# IGOR_1.net
KiCad netlist of a schematic drawn in EAGLE
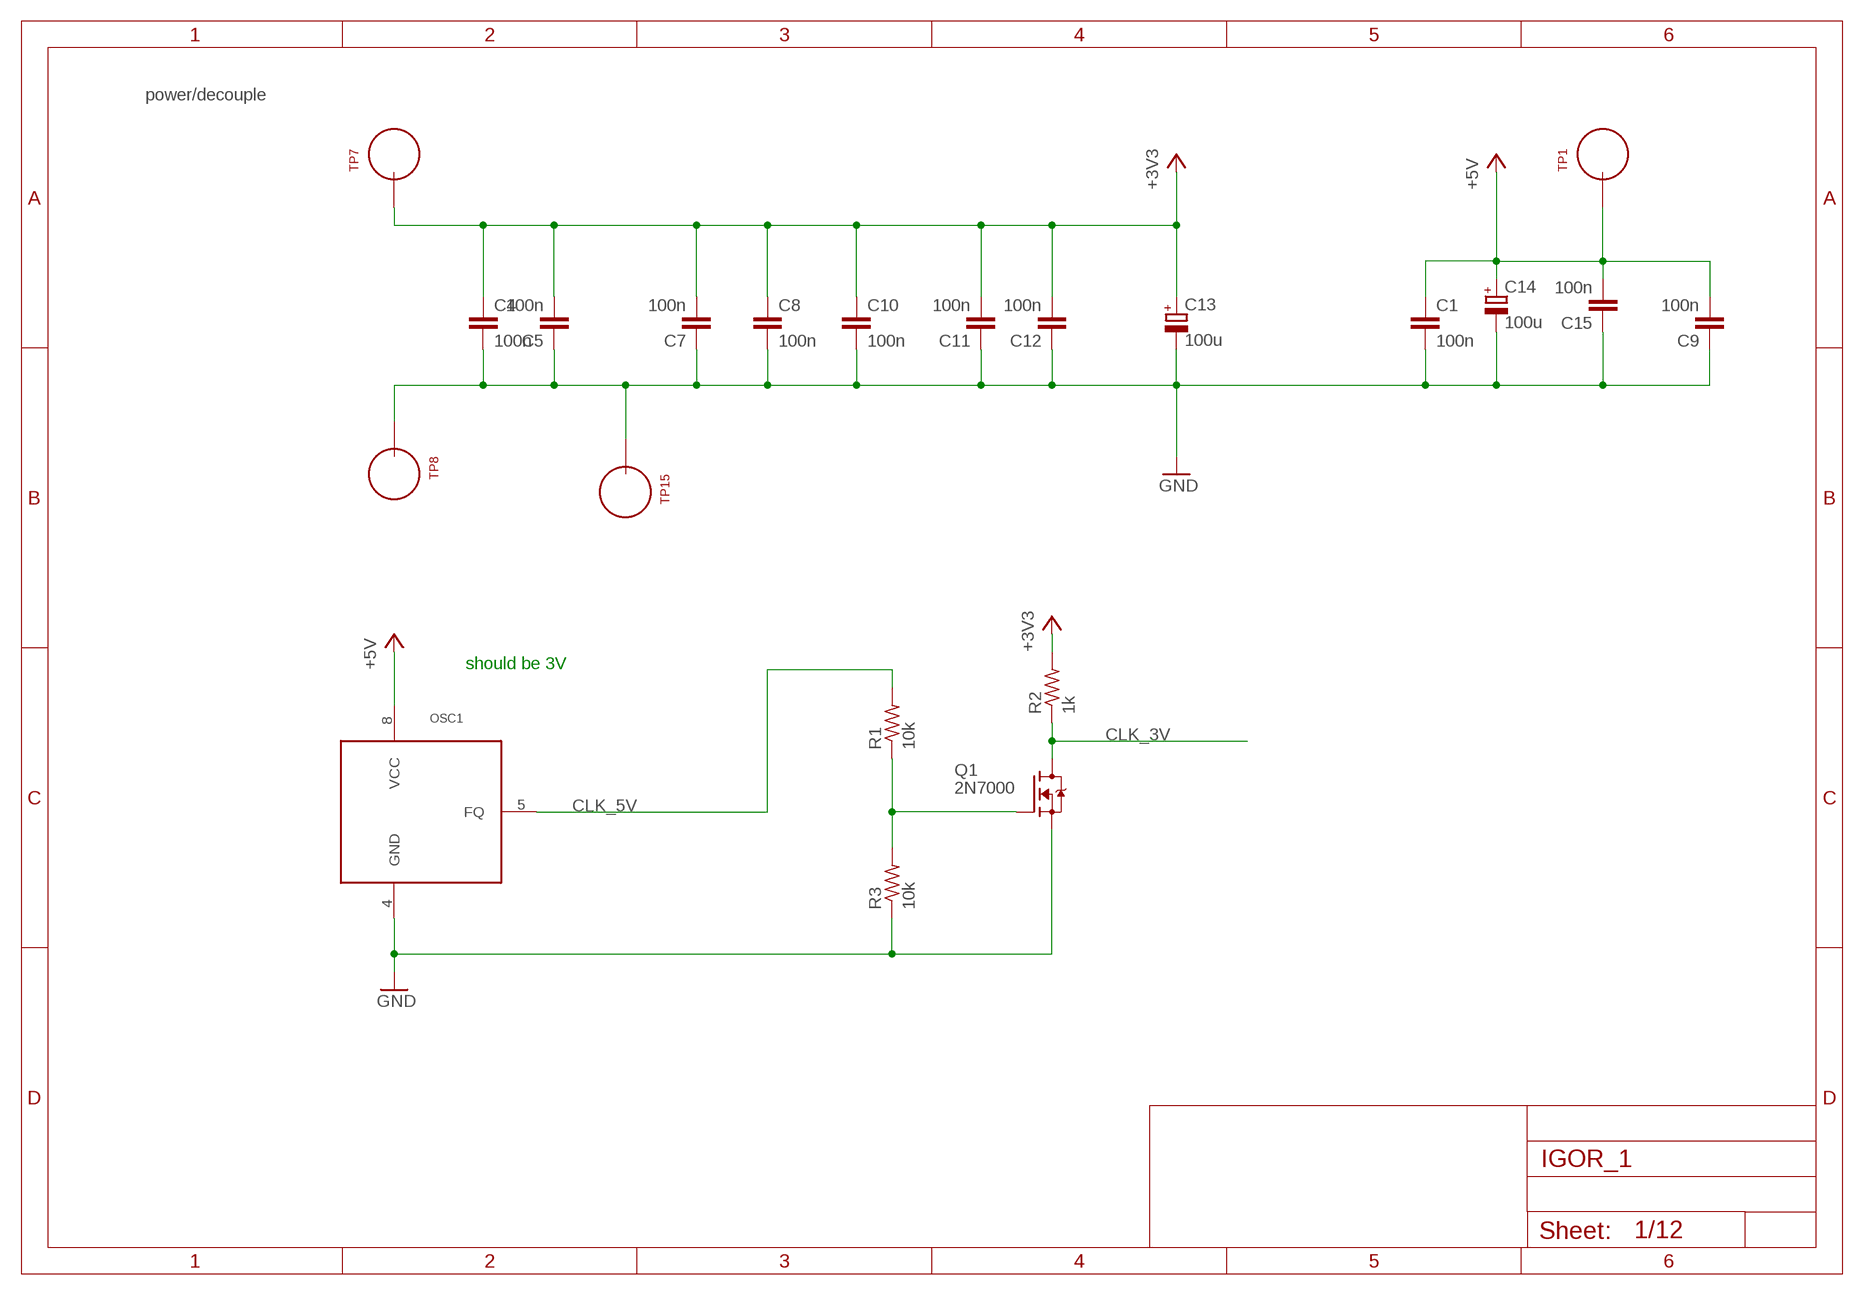
[diagram p0: schematic, sheet 1]
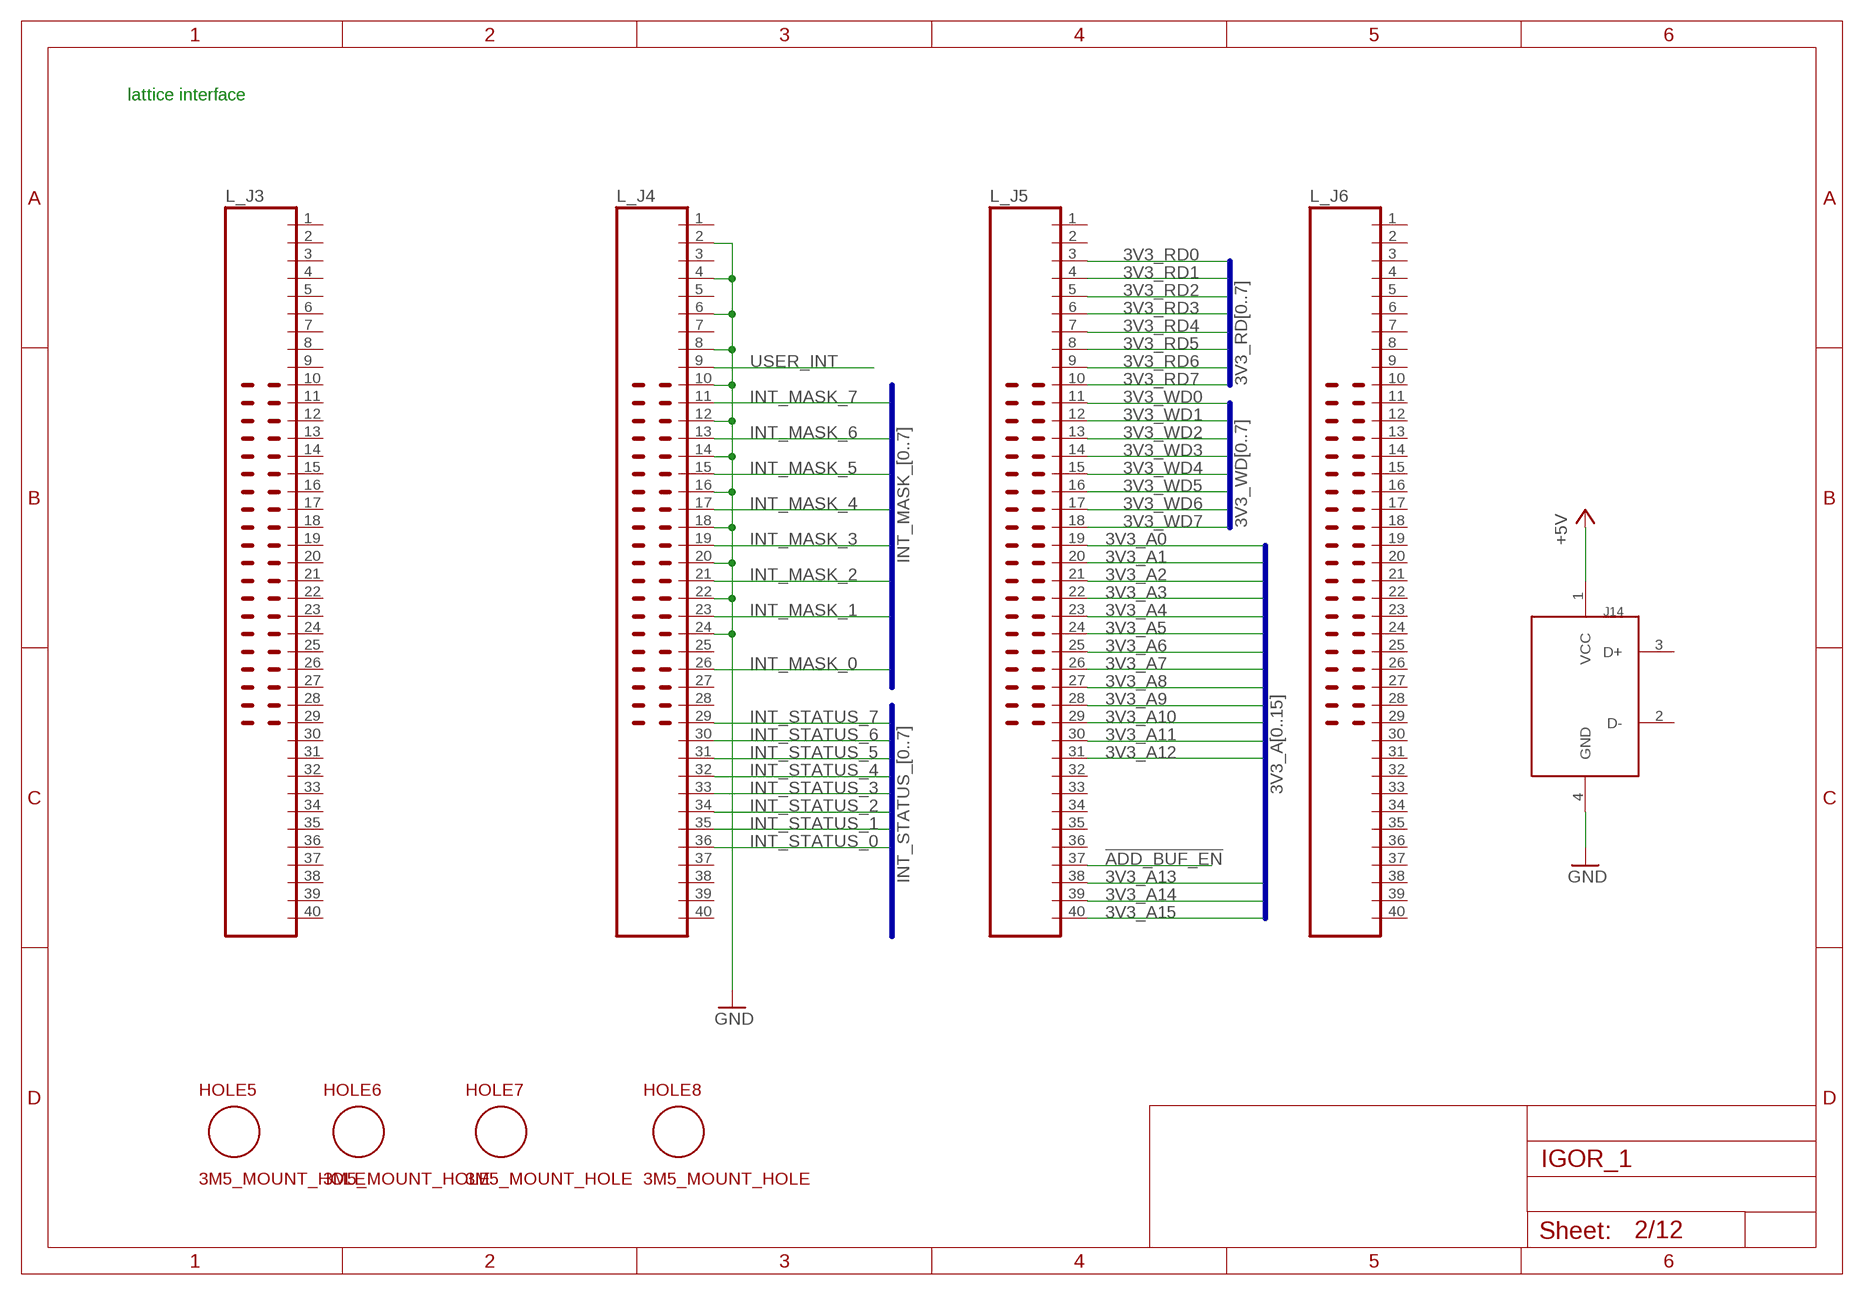
[diagram p1: schematic, sheet 2]
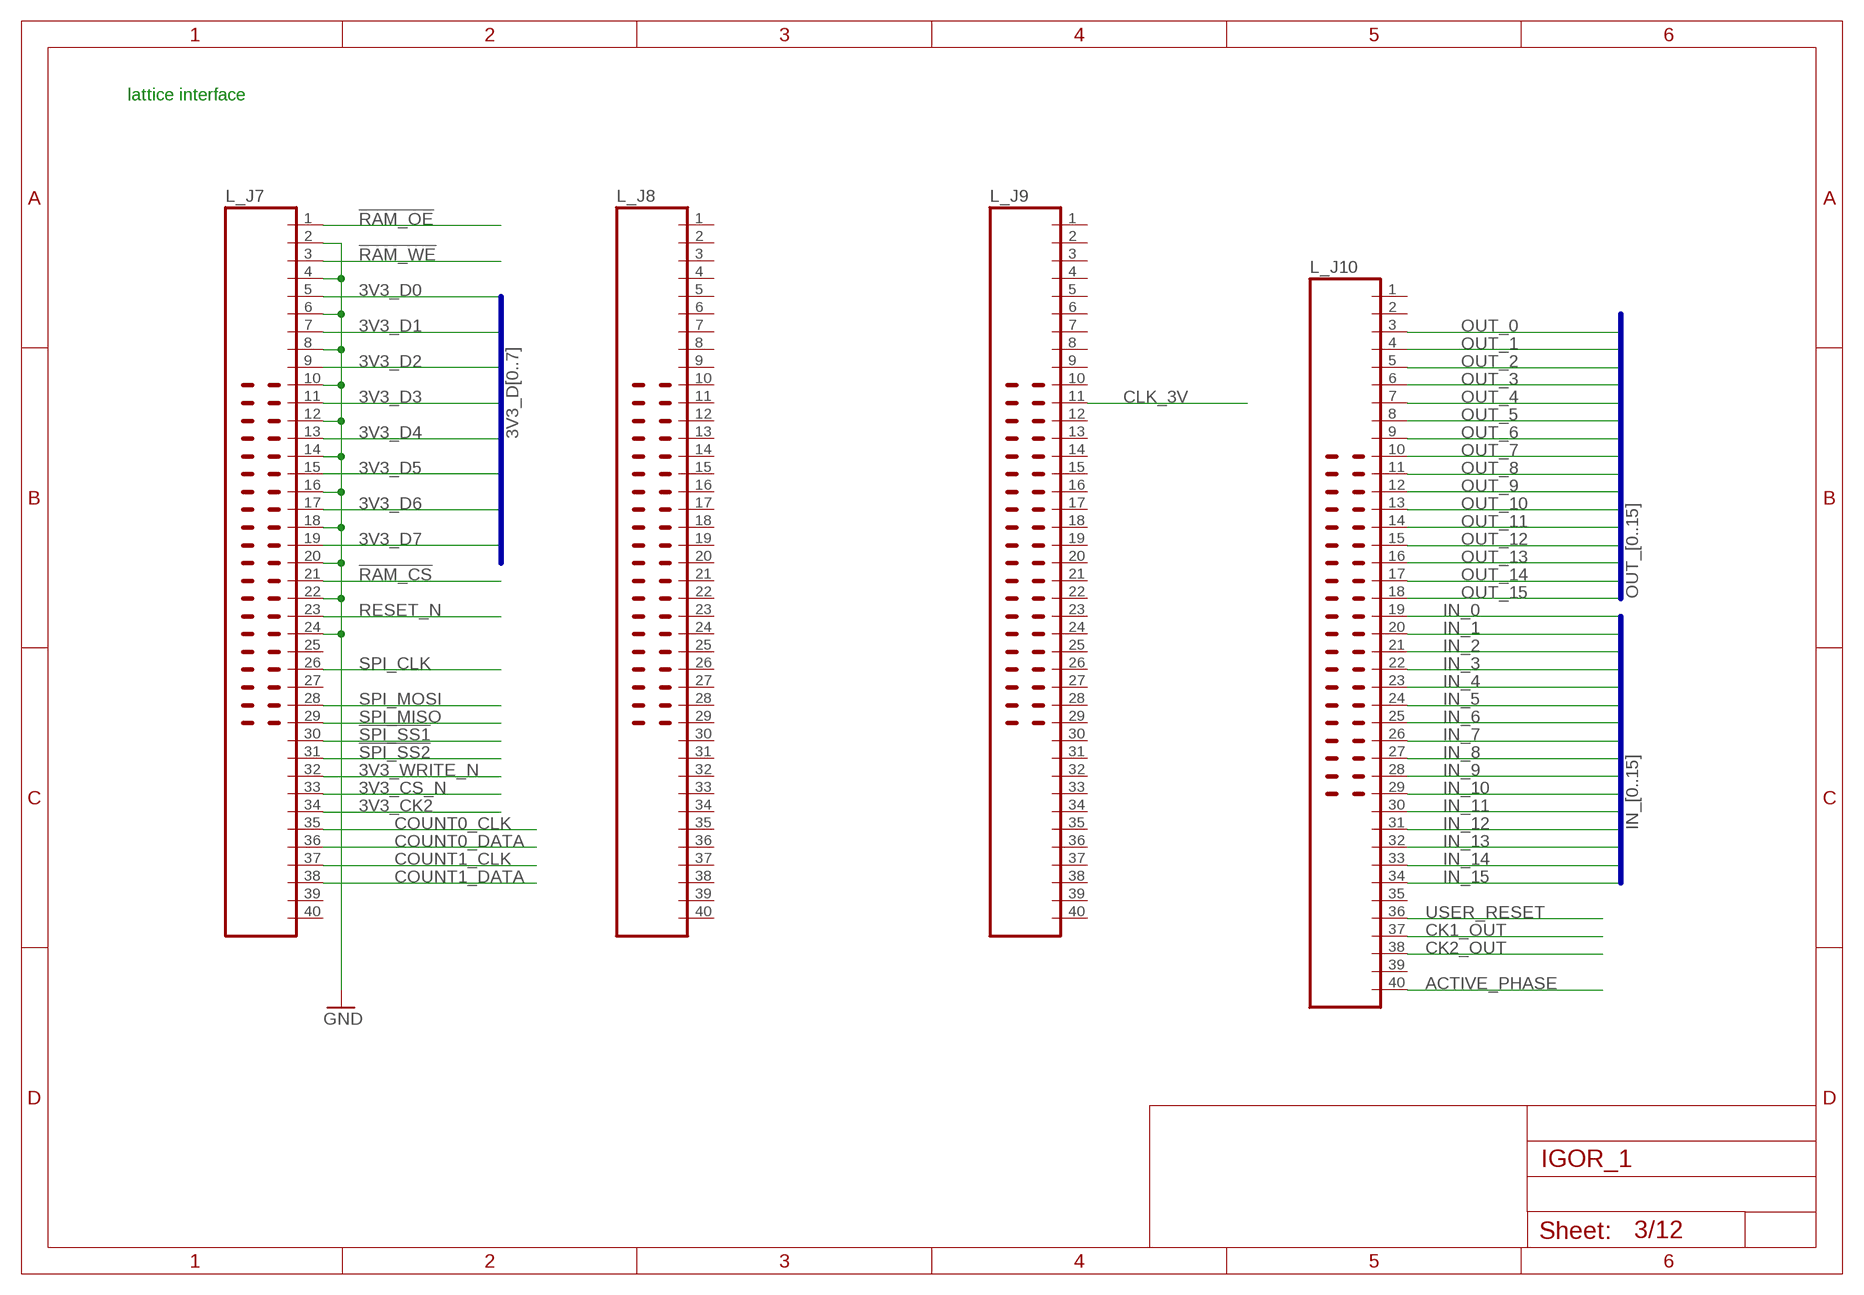
[diagram p2: schematic, sheet 3]
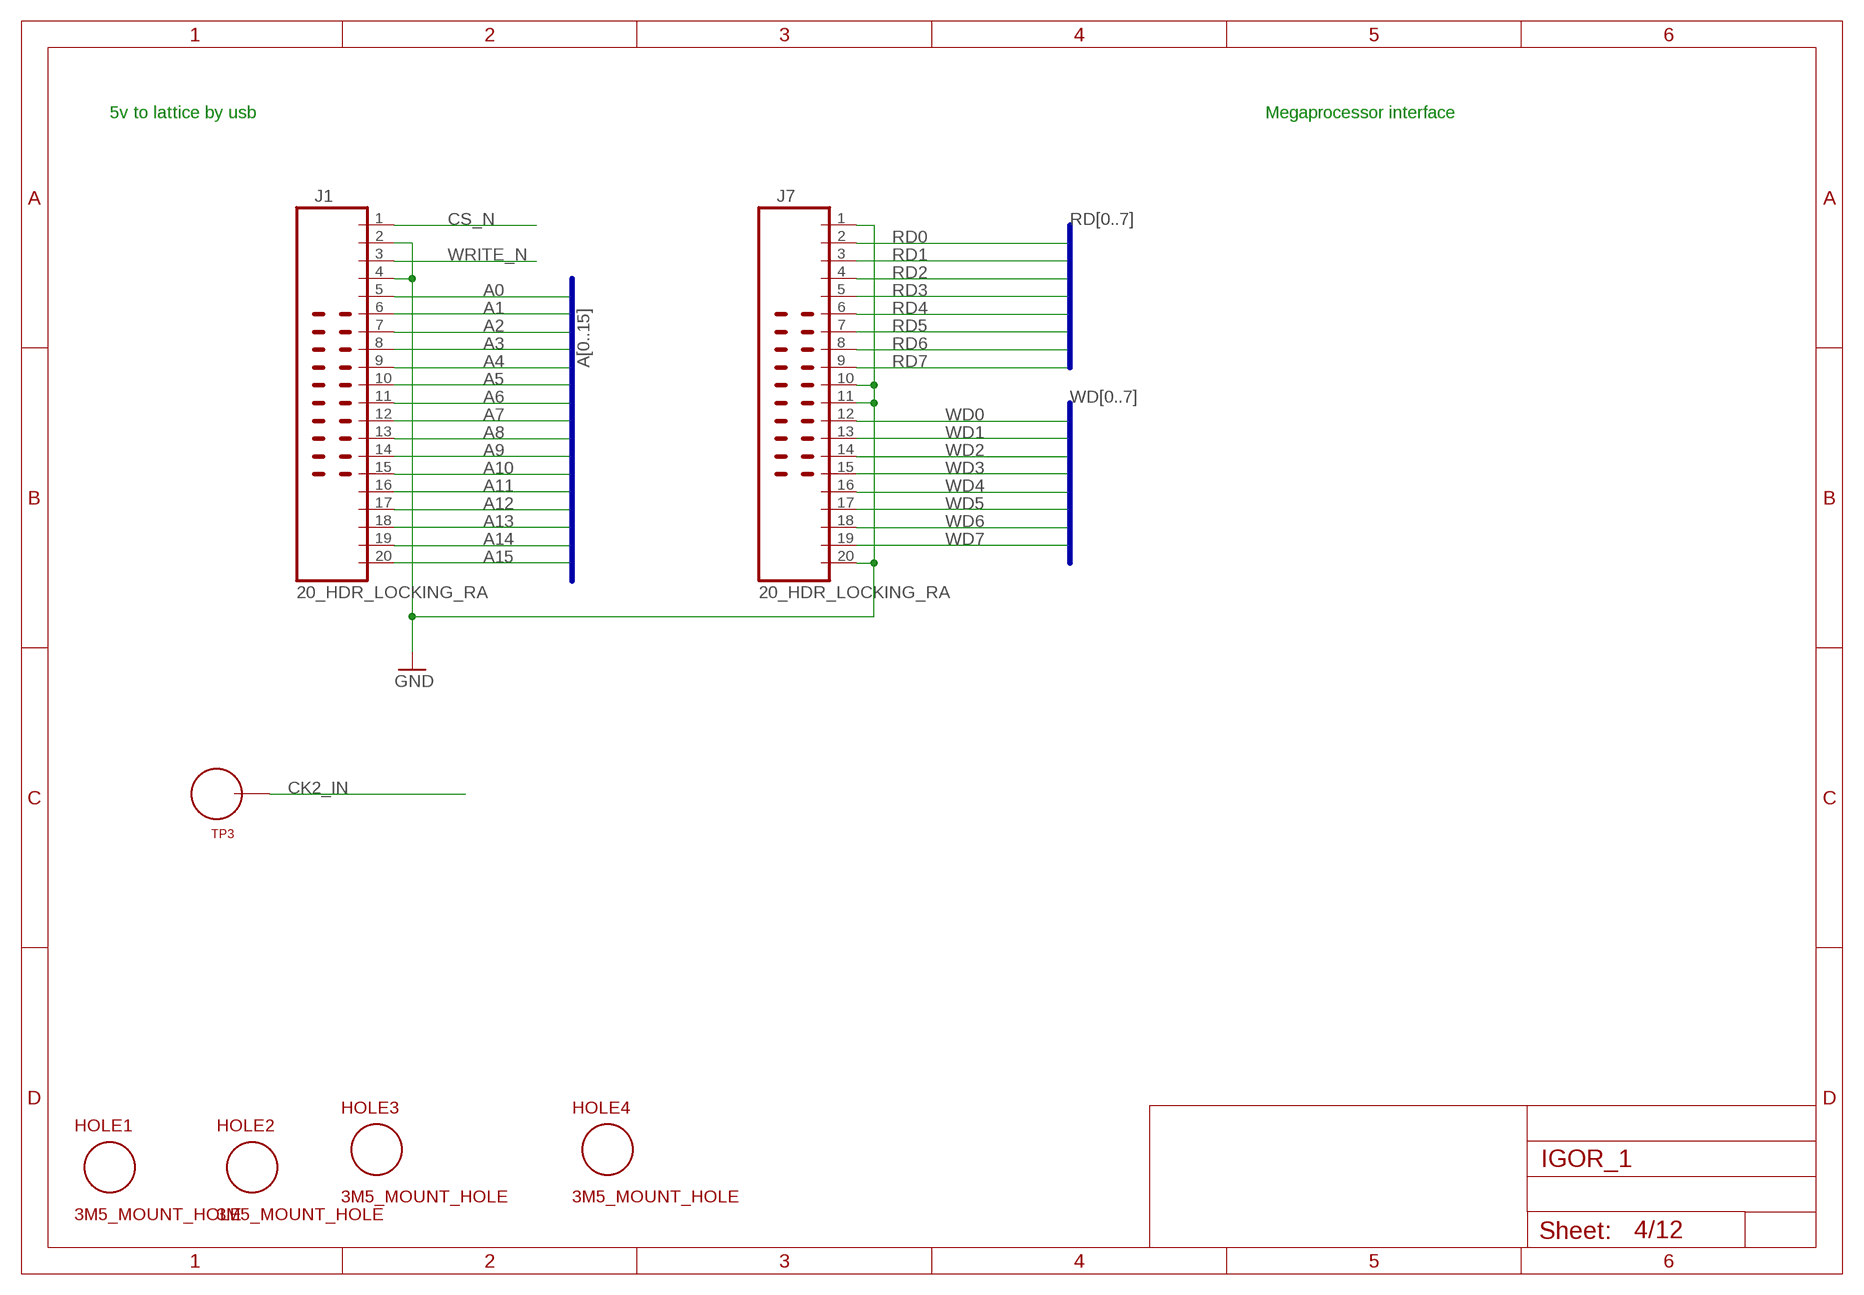
[diagram p3: schematic, sheet 4]
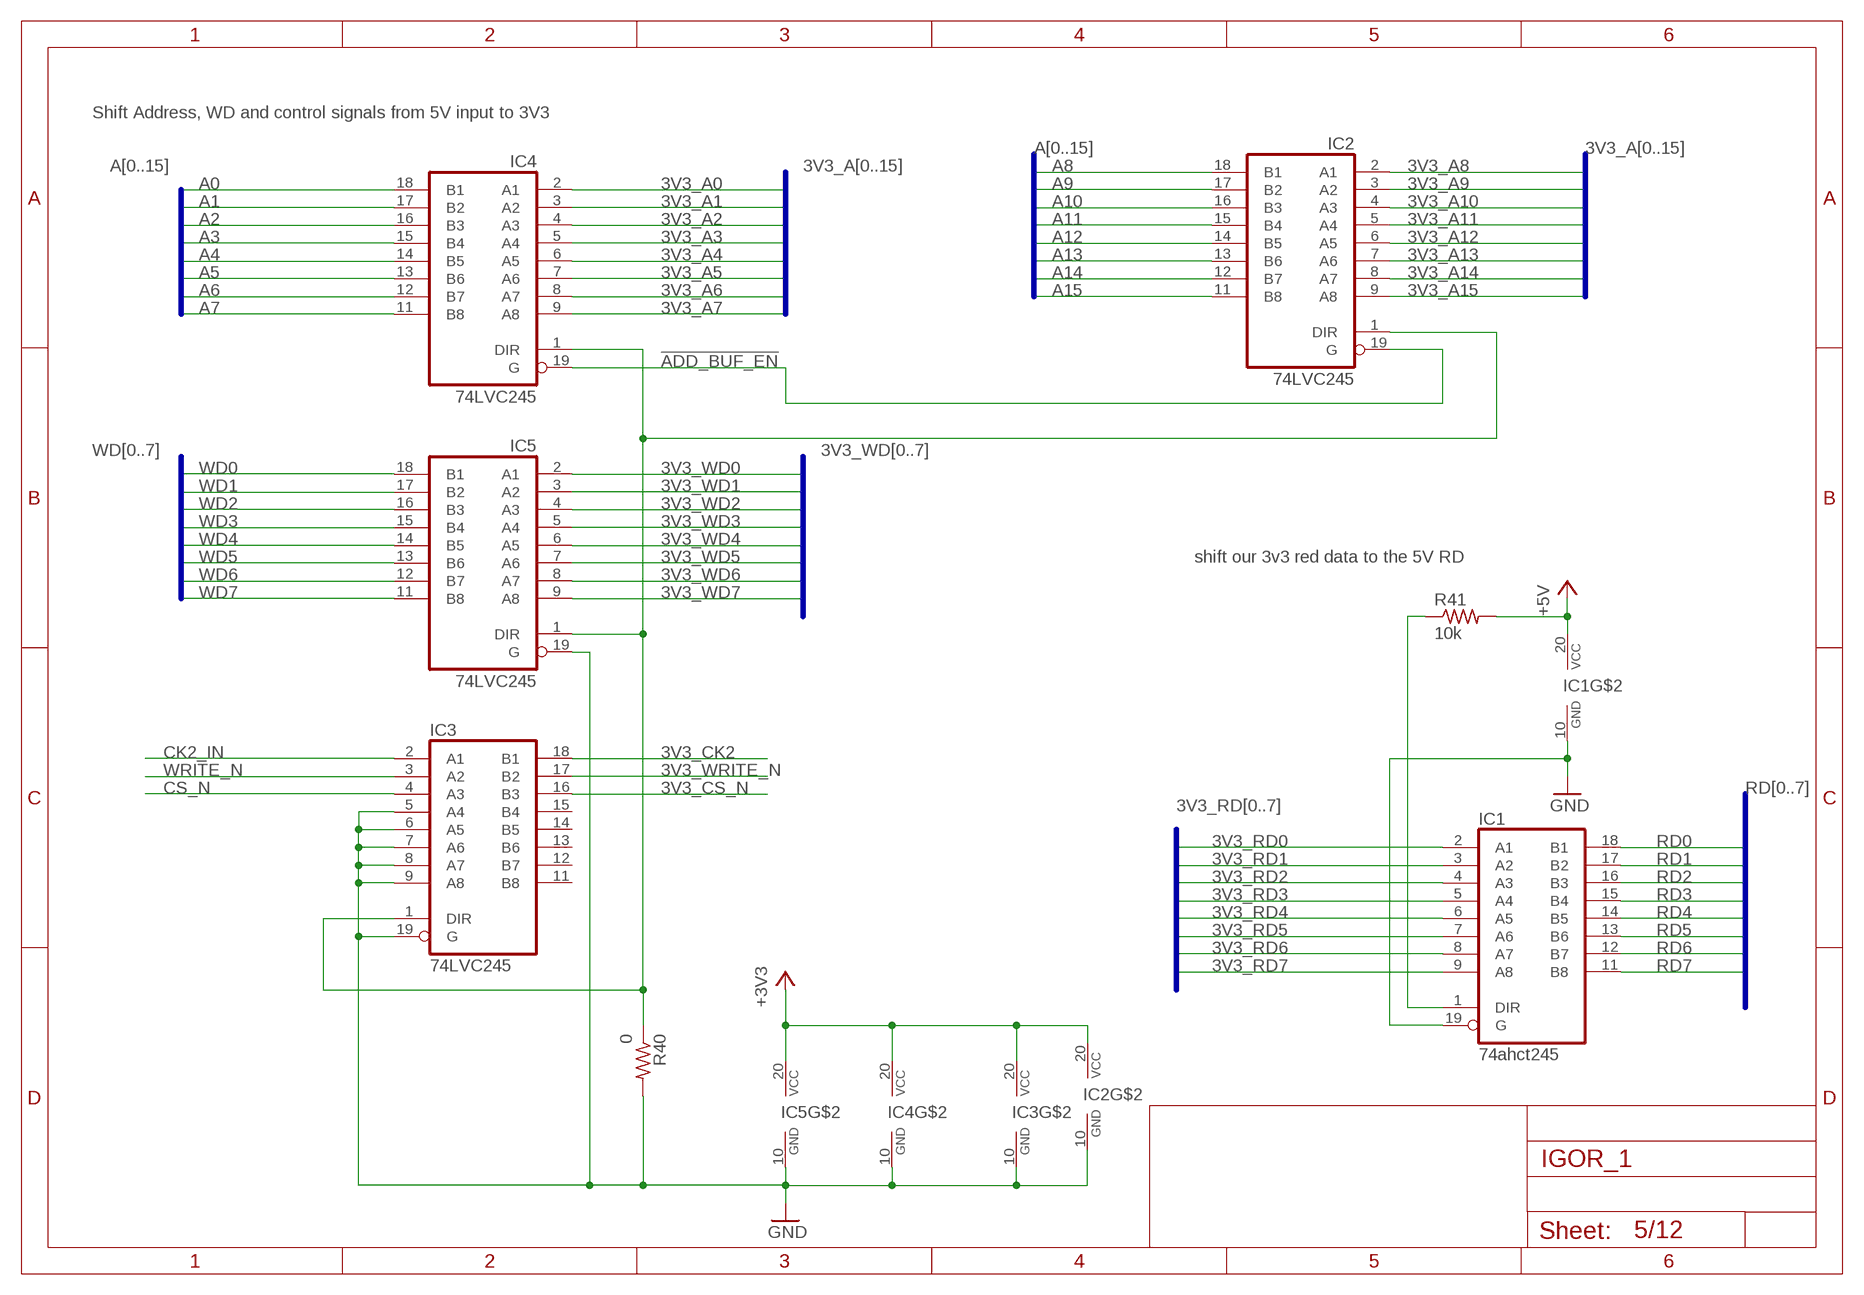
[diagram p4: schematic, sheet 5]
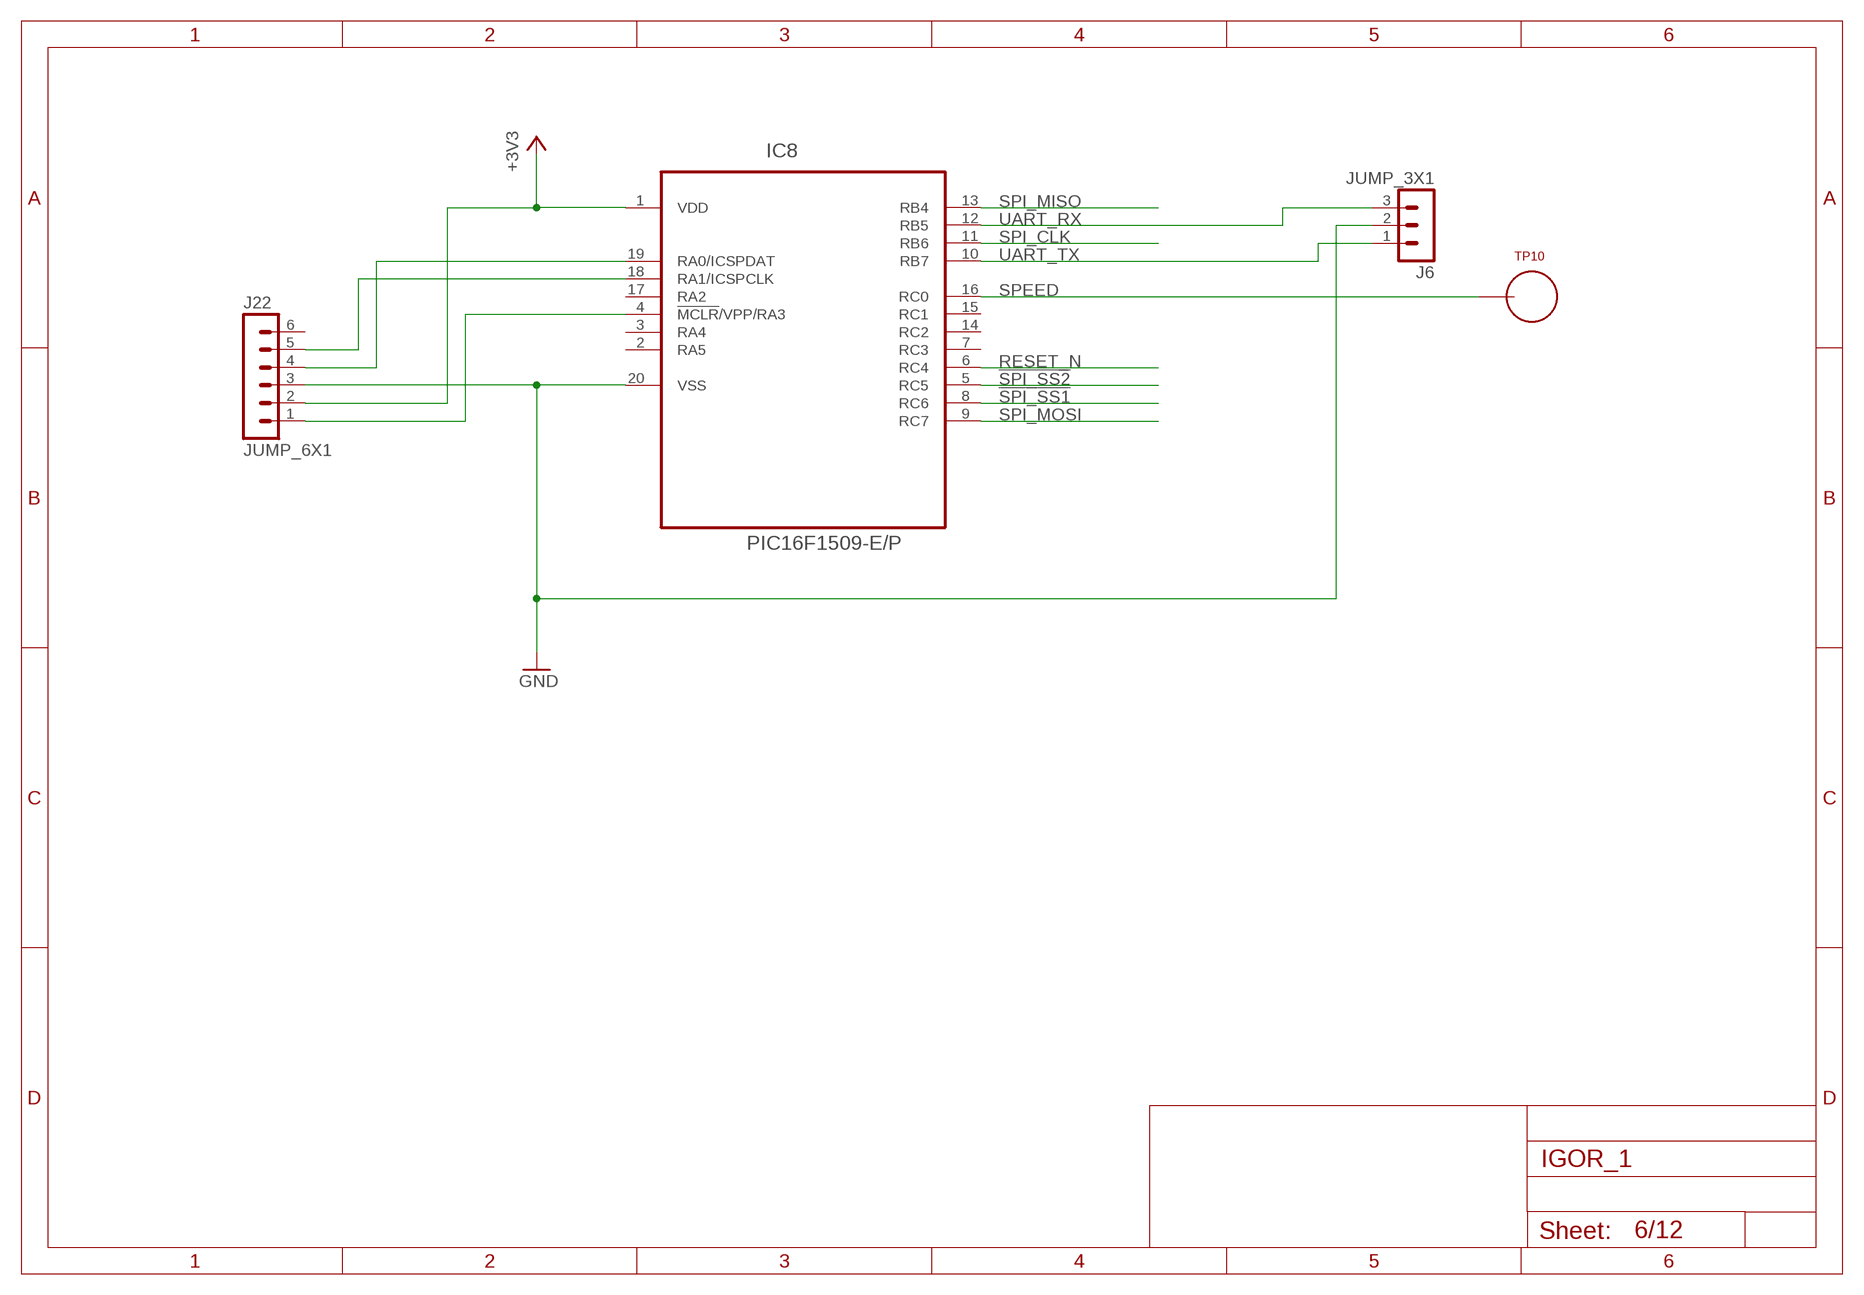
[diagram p5: schematic, sheet 6]
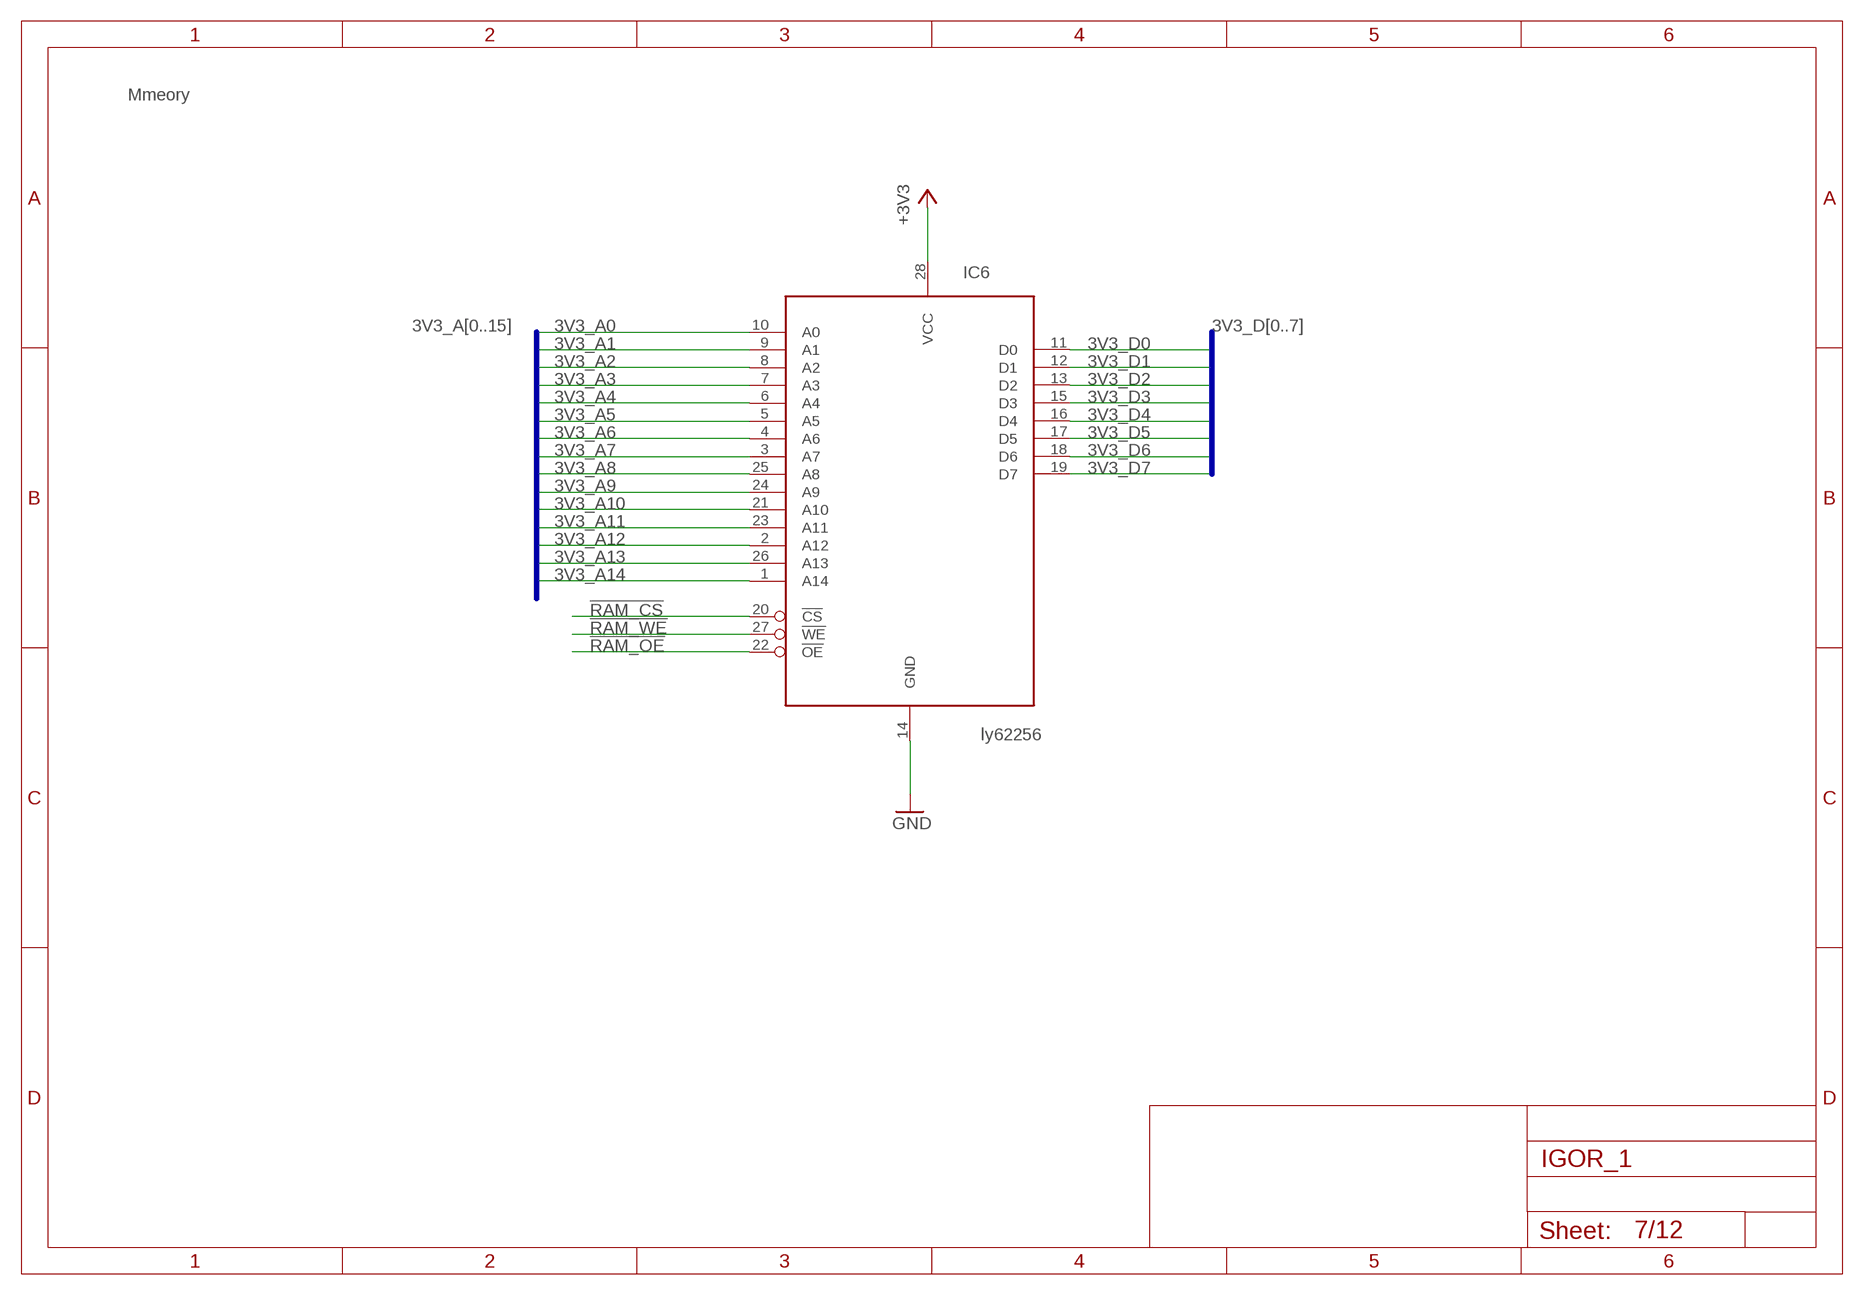
[diagram p6: schematic, sheet 7]
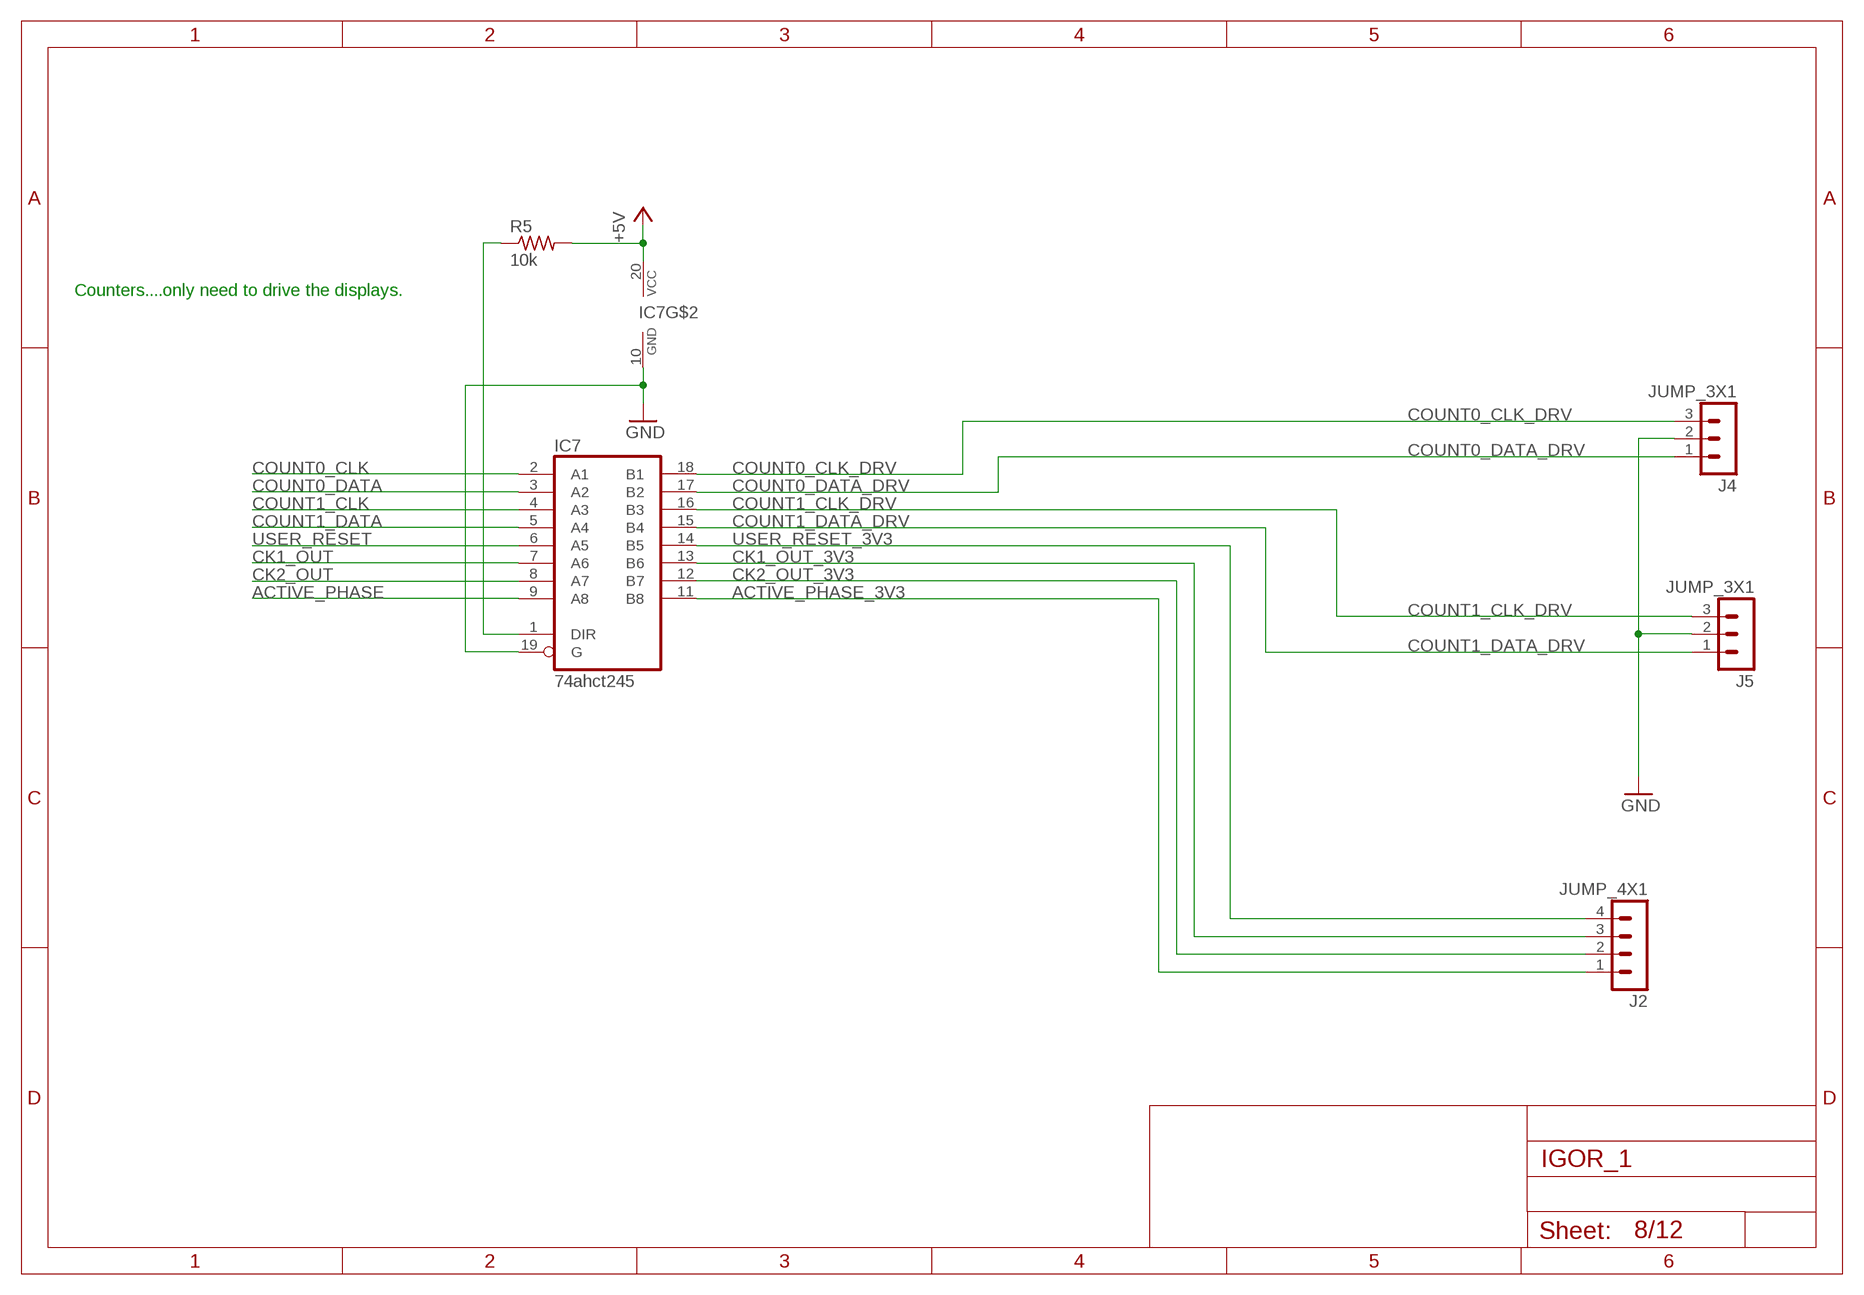
[diagram p7: schematic, sheet 8]
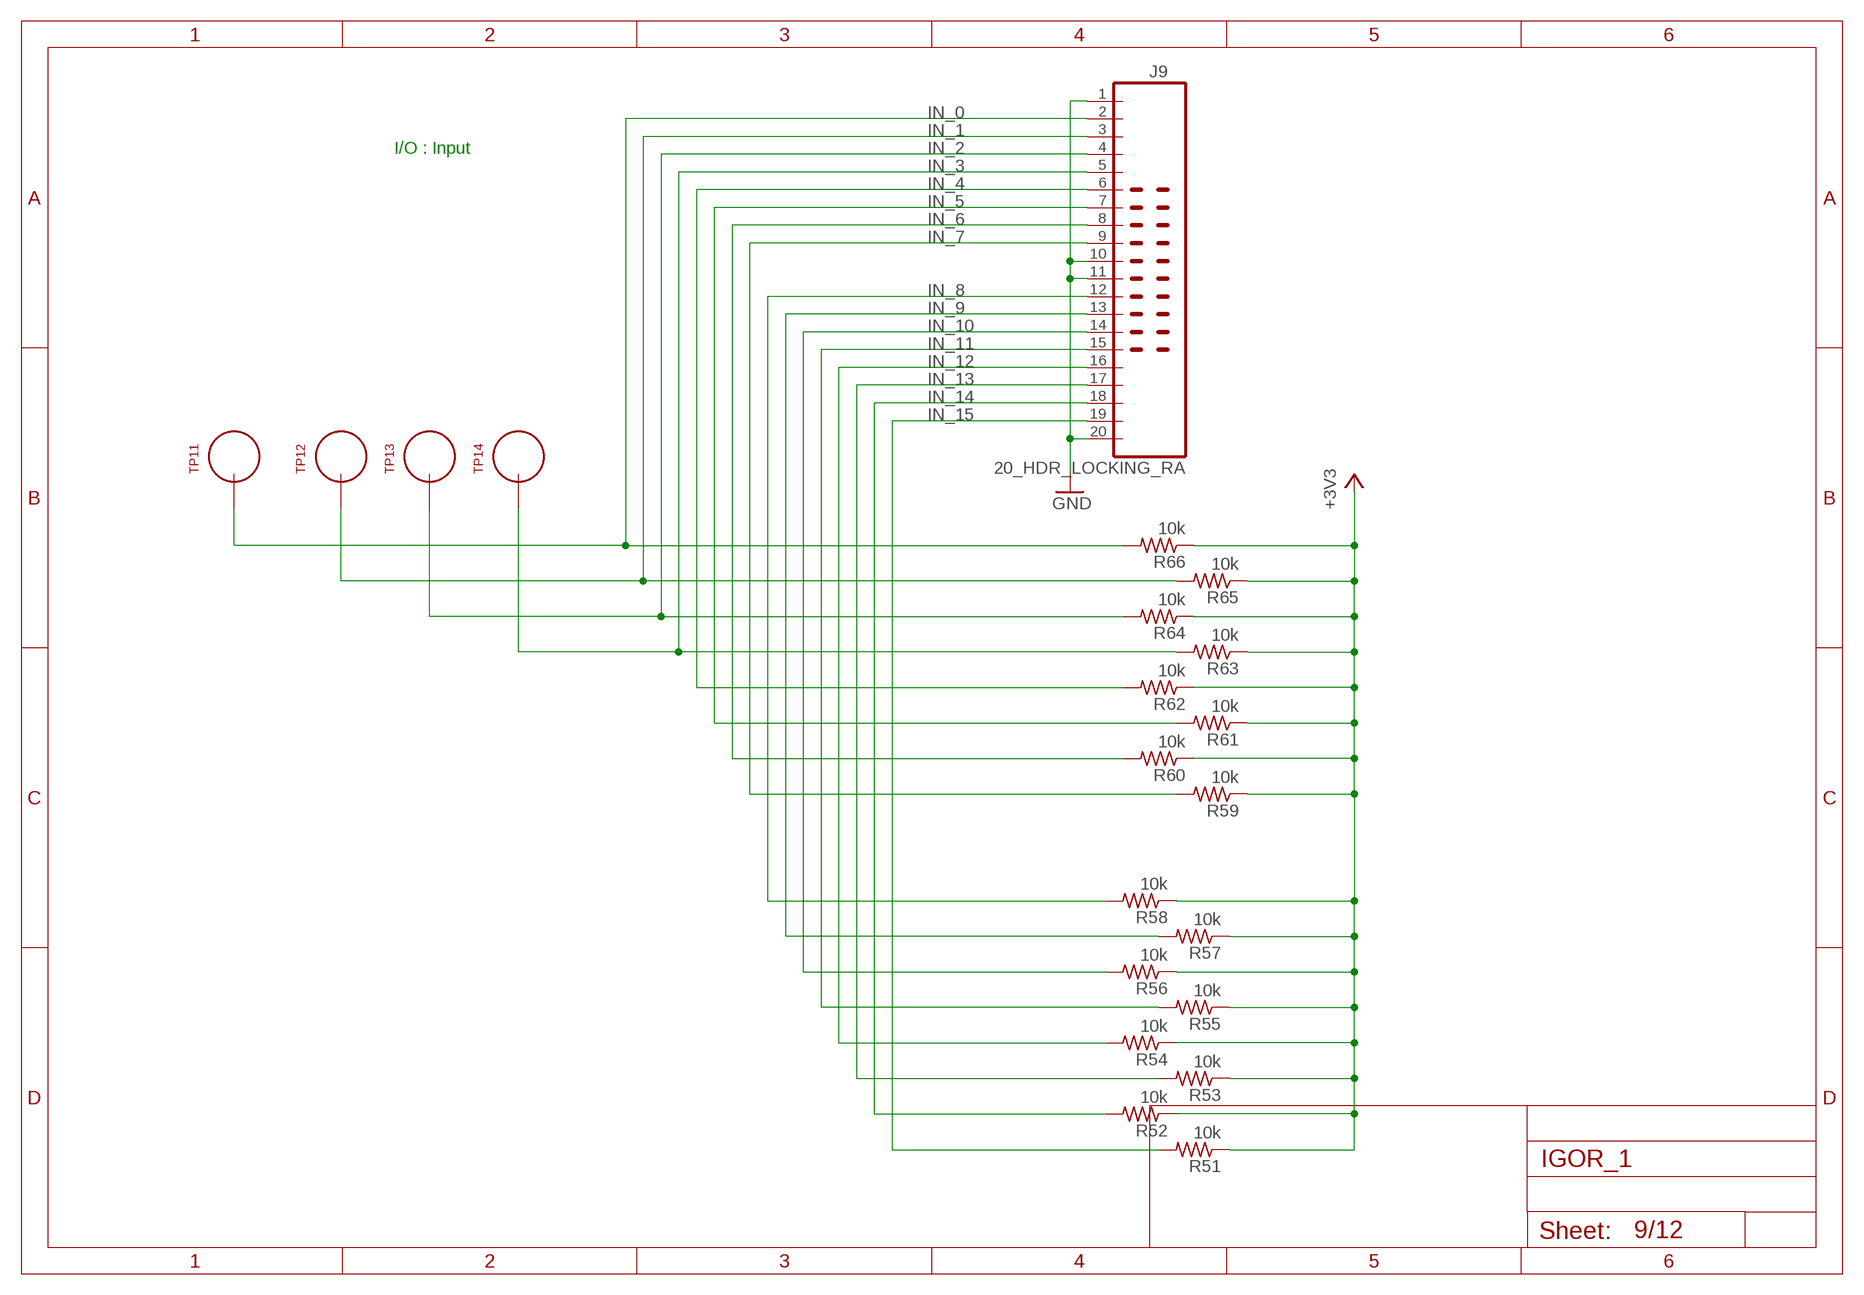
[diagram p8: schematic, sheet 9]
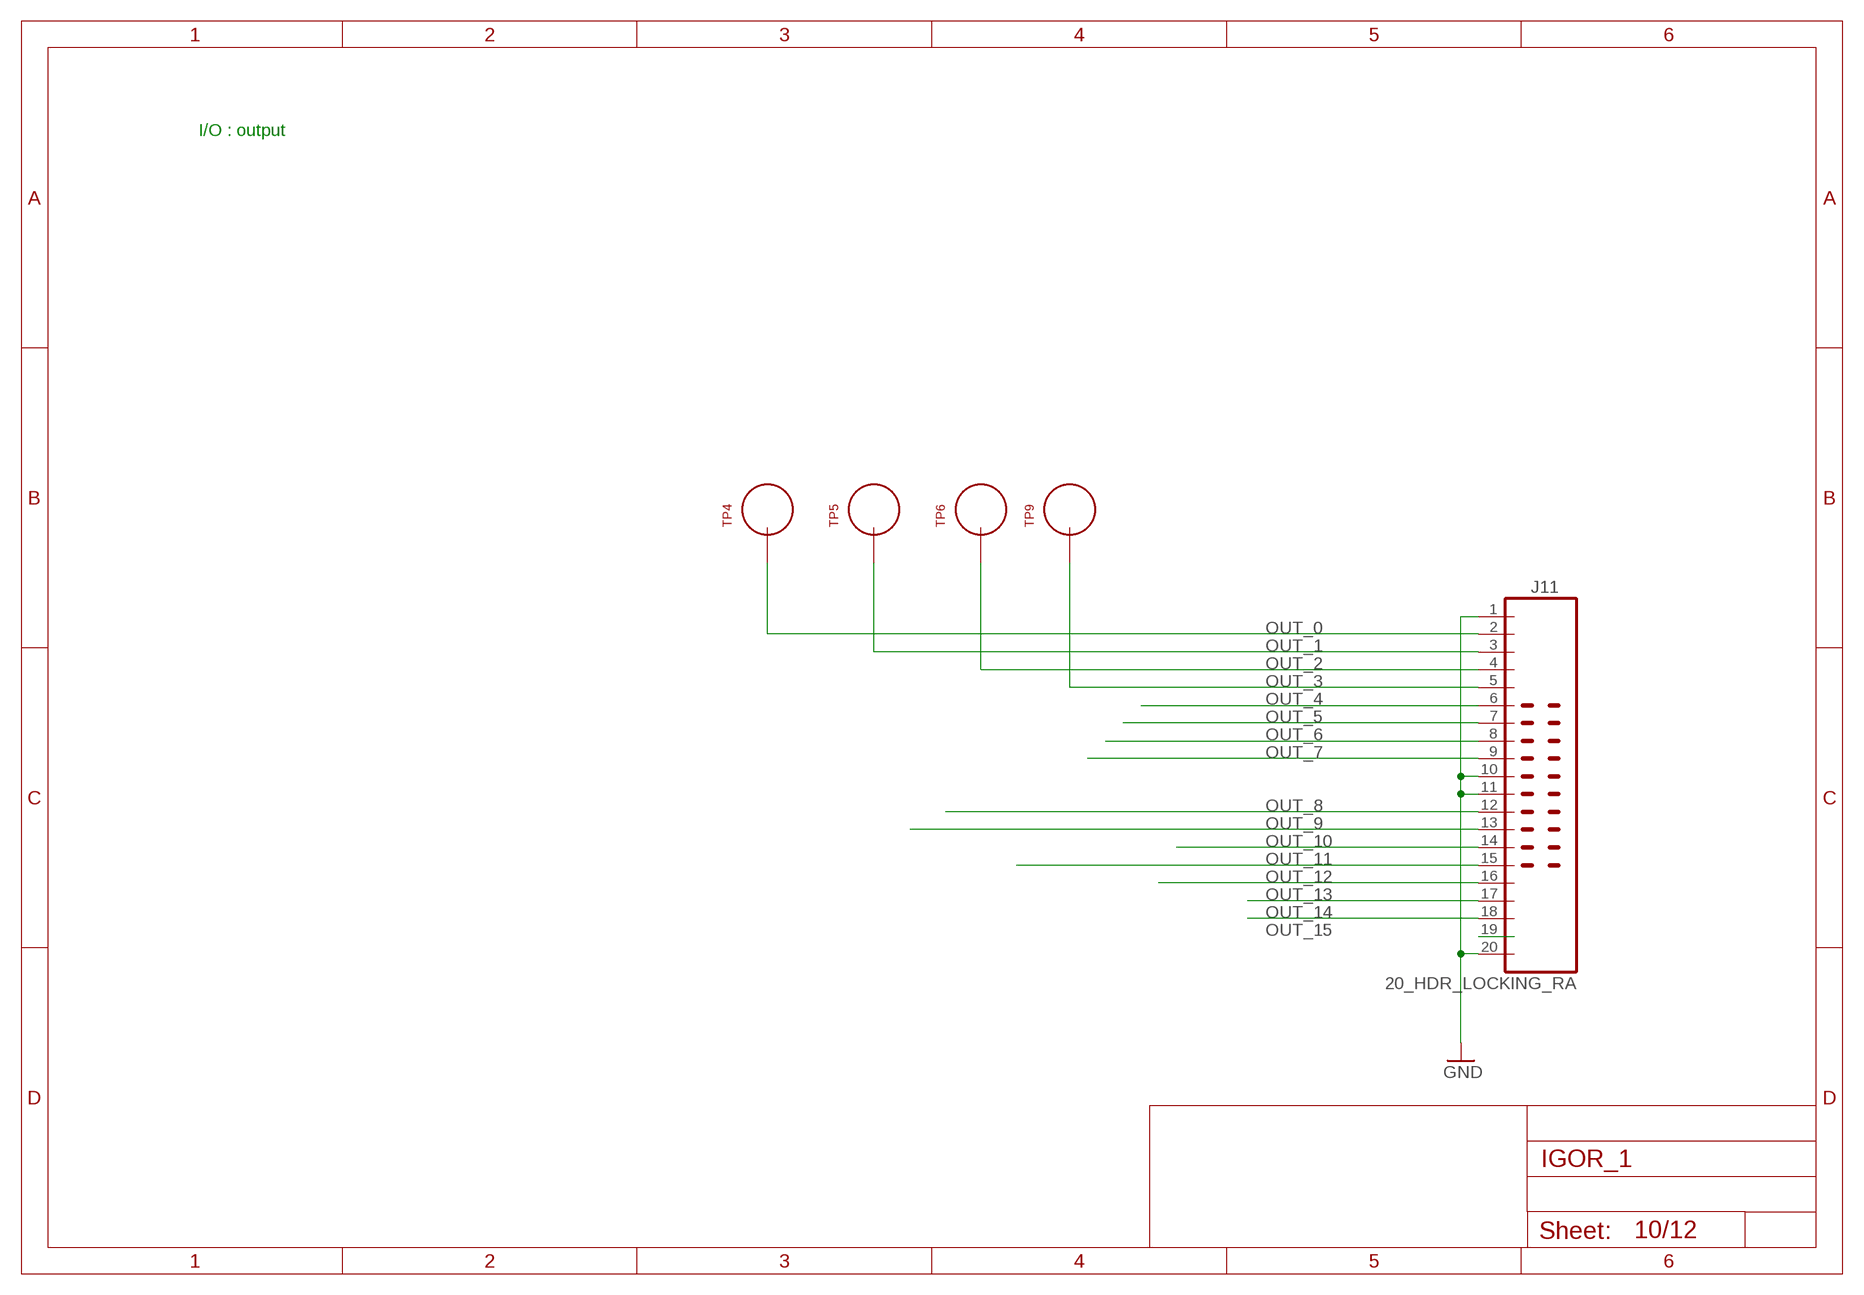
[diagram p9: schematic, sheet 10]
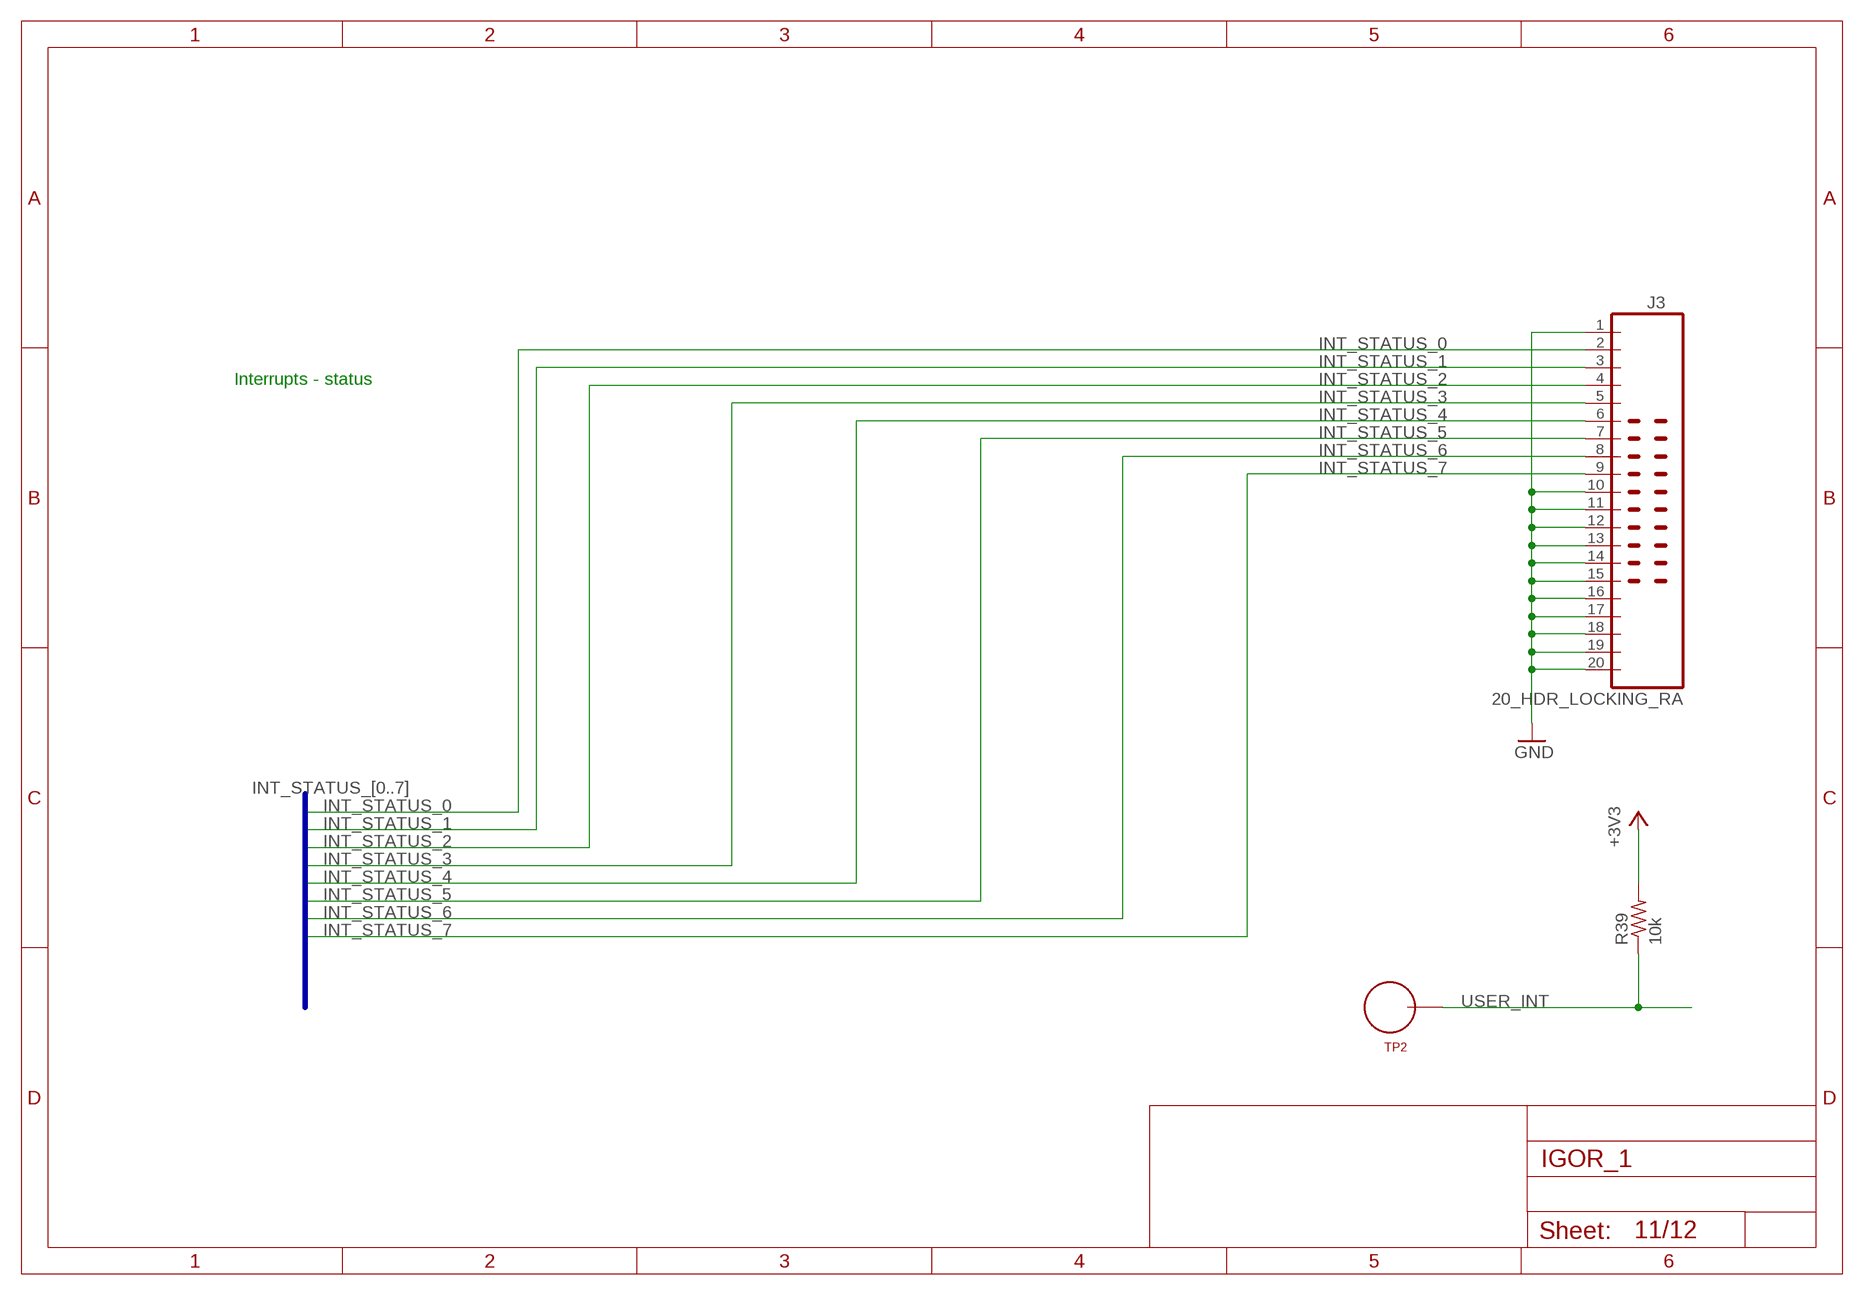
[diagram p10: schematic, sheet 11]
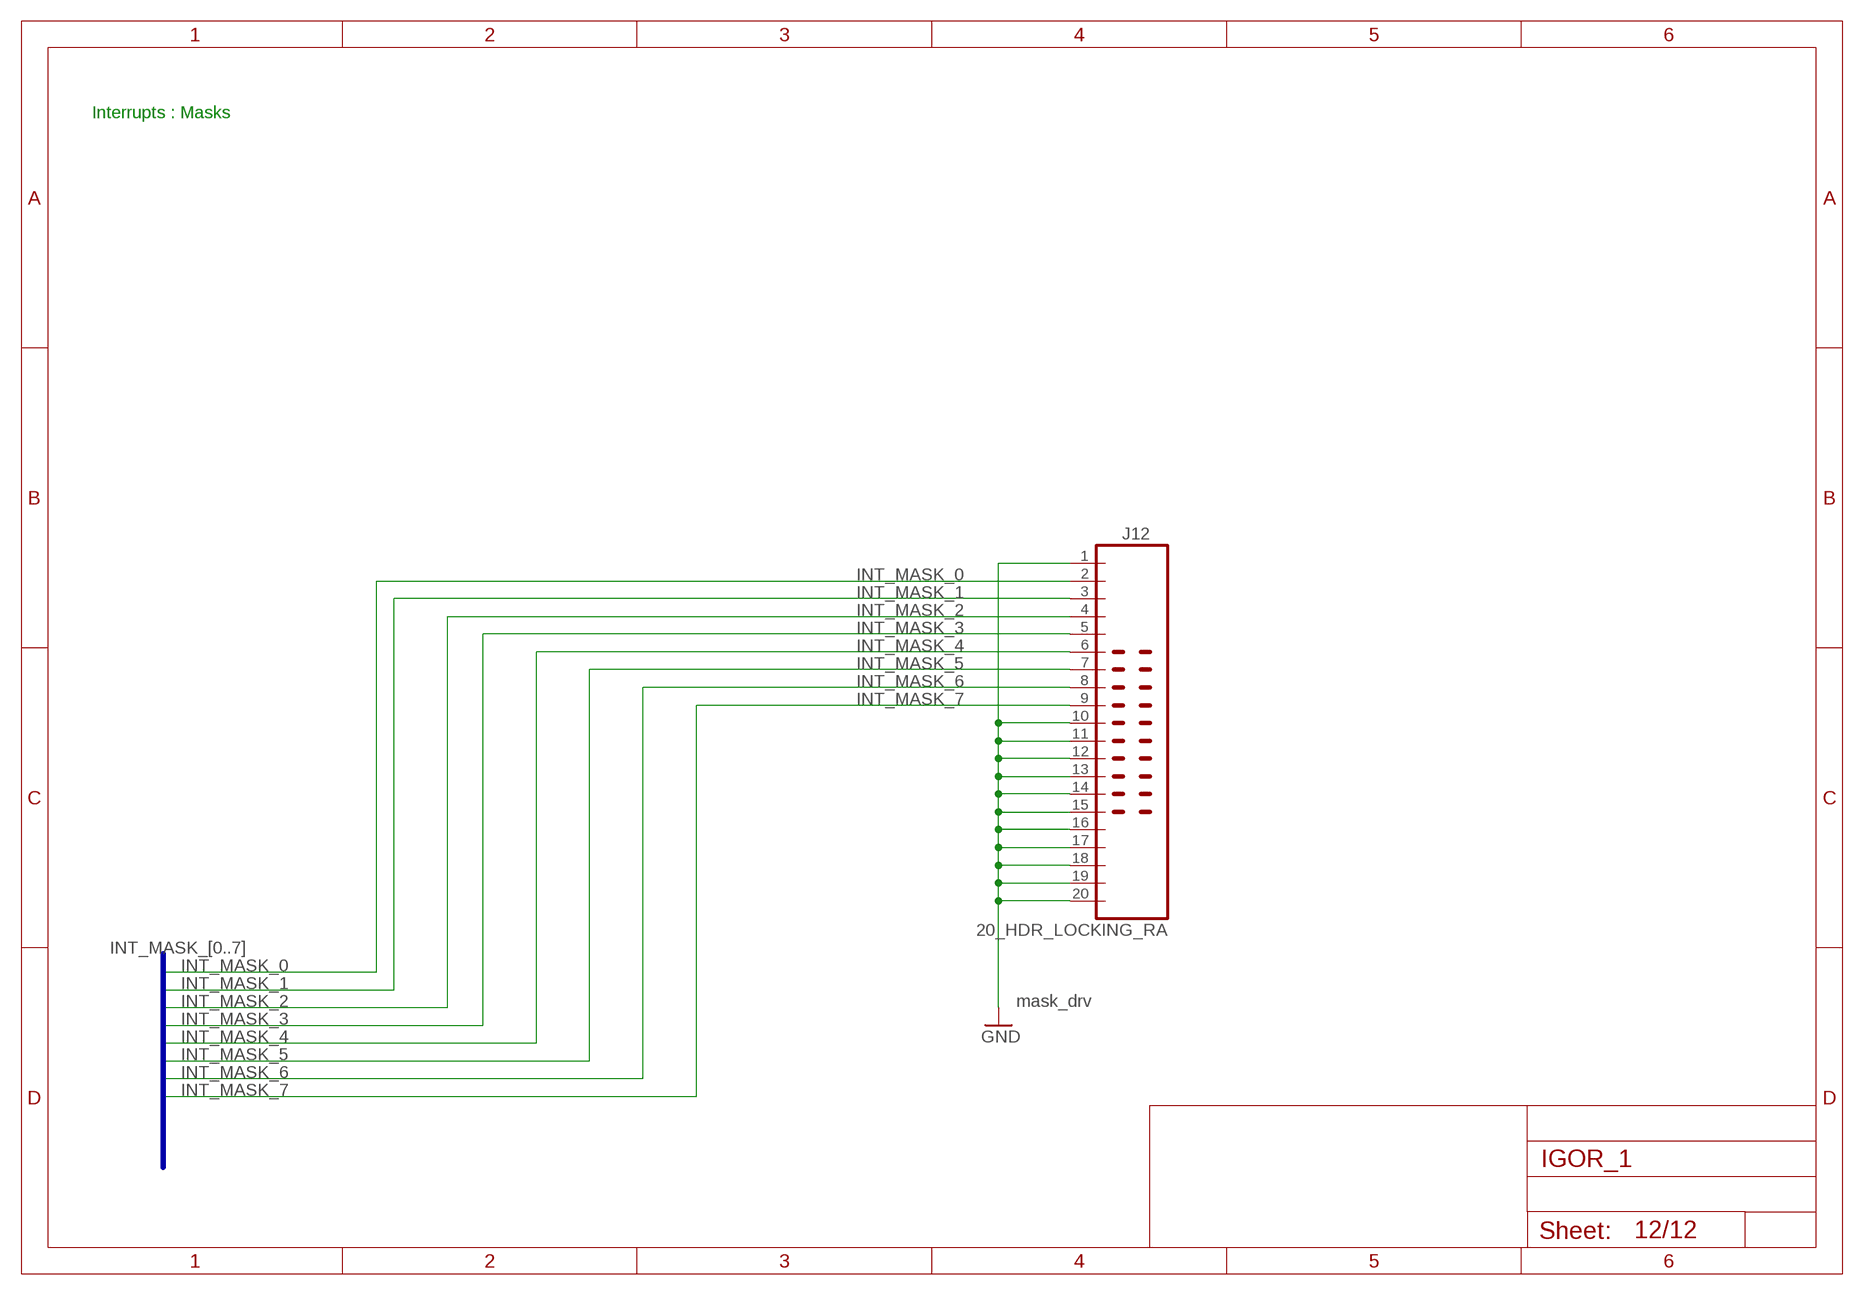
[diagram p11: schematic, sheet 12]

(export (version "E")
  (design (tool "Eeschema 10.0.6"))
  (components
    (comp (ref "IC7")
      (value "74ahct245")
      (footprint "eagle-import:DIP20")
      (libsource (lib "eagle-import") (part "74245"))
    )
    (comp (ref "J2")
      (value "JUMP_4X1")
      (footprint "eagle-import:JUMP_4X1")
      (libsource (lib "eagle-import") (part "JUMP_4X1"))
    )
    (comp (ref "J4")
      (value "JUMP_3X1")
      (footprint "eagle-import:JUMP_3X1")
      (libsource (lib "eagle-import") (part "JUMP_3X1"))
    )
    (comp (ref "J5")
      (value "JUMP_3X1")
      (footprint "eagle-import:JUMP_3X1")
      (libsource (lib "eagle-import") (part "JUMP_3X1"))
    )
    (comp (ref "R5")
      (value "10k")
      (footprint "eagle-import:R_P2INCH")
      (libsource (lib "eagle-import") (part "R_P2INCH"))
    )
    (comp (ref "HOLE5")
      (value "3M5_MOUNT_HOLE")
      (footprint "eagle-import:3P5M_HOLE")
      (libsource (lib "eagle-import") (part "3M5_MOUNT_HOLE"))
    )
    (comp (ref "HOLE6")
      (value "3M5_MOUNT_HOLE")
      (footprint "eagle-import:3P5M_HOLE")
      (libsource (lib "eagle-import") (part "3M5_MOUNT_HOLE"))
    )
    (comp (ref "HOLE7")
      (value "3M5_MOUNT_HOLE")
      (footprint "eagle-import:3P5M_HOLE")
      (libsource (lib "eagle-import") (part "3M5_MOUNT_HOLE"))
    )
    (comp (ref "HOLE8")
      (value "3M5_MOUNT_HOLE")
      (footprint "eagle-import:3P5M_HOLE")
      (libsource (lib "eagle-import") (part "3M5_MOUNT_HOLE"))
    )
    (comp (ref "J14")
      (value "USB_TYPE_A")
      (footprint "eagle-import:USB_TYPE_A")
      (libsource (lib "eagle-import") (part "USB_TYPE_A"))
    )
    (comp (ref "L_J3")
      (value "JUMP_20X2")
      (footprint "eagle-import:JUMP_20X2")
      (libsource (lib "eagle-import") (part "JUMP_20X2"))
    )
    (comp (ref "L_J4")
      (value "JUMP_20X2")
      (footprint "eagle-import:JUMP_20X2")
      (libsource (lib "eagle-import") (part "JUMP_20X2"))
    )
    (comp (ref "L_J5")
      (value "JUMP_20X2")
      (footprint "eagle-import:JUMP_20X2")
      (libsource (lib "eagle-import") (part "JUMP_20X2"))
    )
    (comp (ref "L_J6")
      (value "JUMP_20X2")
      (footprint "eagle-import:JUMP_20X2")
      (libsource (lib "eagle-import") (part "JUMP_20X2"))
    )
    (comp (ref "J11")
      (value "20_HDR_LOCKING_RA")
      (footprint "eagle-import:20_HDR_LOCKING_RA")
      (libsource (lib "eagle-import") (part "20_HDR_LOCKING_RA"))
    )
    (comp (ref "TP4")
      (value "TEST_LOOP")
      (footprint "eagle-import:TEST_LOOP")
      (libsource (lib "eagle-import") (part "TEST_LOOP"))
    )
    (comp (ref "TP5")
      (value "TEST_LOOP")
      (footprint "eagle-import:TEST_LOOP")
      (libsource (lib "eagle-import") (part "TEST_LOOP"))
    )
    (comp (ref "TP6")
      (value "TEST_LOOP")
      (footprint "eagle-import:TEST_LOOP")
      (libsource (lib "eagle-import") (part "TEST_LOOP"))
    )
    (comp (ref "TP9")
      (value "TEST_LOOP")
      (footprint "eagle-import:TEST_LOOP")
      (libsource (lib "eagle-import") (part "TEST_LOOP"))
    )
    (comp (ref "C1")
      (value "100n")
      (footprint "eagle-import:CAP_P2INCH")
      (libsource (lib "eagle-import") (part "C_P2INCH"))
    )
    (comp (ref "C4")
      (value "100n")
      (footprint "eagle-import:CAP_P2INCH")
      (libsource (lib "eagle-import") (part "C_P2INCH"))
    )
    (comp (ref "C5")
      (value "100n")
      (footprint "eagle-import:CAP_P2INCH")
      (libsource (lib "eagle-import") (part "C_P2INCH"))
    )
    (comp (ref "C7")
      (value "100n")
      (footprint "eagle-import:CAP_P2INCH")
      (libsource (lib "eagle-import") (part "C_P2INCH"))
    )
    (comp (ref "C8")
      (value "100n")
      (footprint "eagle-import:CAP_P2INCH")
      (libsource (lib "eagle-import") (part "C_P2INCH"))
    )
    (comp (ref "C9")
      (value "100n")
      (footprint "eagle-import:CAP_P2INCH")
      (libsource (lib "eagle-import") (part "C_P2INCH"))
    )
    (comp (ref "C10")
      (value "100n")
      (footprint "eagle-import:CAP_P2INCH")
      (libsource (lib "eagle-import") (part "C_P2INCH"))
    )
    (comp (ref "C11")
      (value "100n")
      (footprint "eagle-import:CAP_P2INCH")
      (libsource (lib "eagle-import") (part "C_P2INCH"))
    )
    (comp (ref "C12")
      (value "100n")
      (footprint "eagle-import:CAP_P2INCH")
      (libsource (lib "eagle-import") (part "C_P2INCH"))
    )
    (comp (ref "C13")
      (value "100u")
      (footprint "eagle-import:POLARISED_CAP_2P5_6P3MM")
      (libsource (lib "eagle-import") (part "POLARISED_CAP_2P5_6P3MM"))
    )
    (comp (ref "C14")
      (value "100u")
      (footprint "eagle-import:POLARISED_CAP_2P5_6P3MM")
      (libsource (lib "eagle-import") (part "POLARISED_CAP_2P5_6P3MM"))
    )
    (comp (ref "C15")
      (value "100n")
      (footprint "eagle-import:CAP_P2INCH")
      (libsource (lib "eagle-import") (part "C_P2INCH"))
    )
    (comp (ref "OSC1")
      (value "OSC_12P9_MM")
      (footprint "eagle-import:OSC_12P9_MM")
      (libsource (lib "eagle-import") (part "OSC_12P9_MM"))
    )
    (comp (ref "Q1")
      (value "2N7000")
      (footprint "eagle-import:TO92-DGS")
      (libsource (lib "eagle-import") (part "2N7000"))
    )
    (comp (ref "R1")
      (value "10k")
      (footprint "eagle-import:R_P2INCH")
      (libsource (lib "eagle-import") (part "R_P2INCH"))
    )
    (comp (ref "R2")
      (value "1k")
      (footprint "eagle-import:R_P2INCH")
      (libsource (lib "eagle-import") (part "R_P2INCH"))
    )
    (comp (ref "R3")
      (value "10k")
      (footprint "eagle-import:R_P2INCH")
      (libsource (lib "eagle-import") (part "R_P2INCH"))
    )
    (comp (ref "TP1")
      (value "TEST_LOOP")
      (footprint "eagle-import:TEST_LOOP")
      (libsource (lib "eagle-import") (part "TEST_LOOP"))
    )
    (comp (ref "TP7")
      (value "TEST_LOOP")
      (footprint "eagle-import:TEST_LOOP")
      (libsource (lib "eagle-import") (part "TEST_LOOP"))
    )
    (comp (ref "TP8")
      (value "TEST_LOOP")
      (footprint "eagle-import:TEST_LOOP")
      (libsource (lib "eagle-import") (part "TEST_LOOP"))
    )
    (comp (ref "TP15")
      (value "TEST_LOOP")
      (footprint "eagle-import:TEST_LOOP")
      (libsource (lib "eagle-import") (part "TEST_LOOP"))
    )
    (comp (ref "L_J7")
      (value "JUMP_20X2")
      (footprint "eagle-import:JUMP_20X2")
      (libsource (lib "eagle-import") (part "JUMP_20X2"))
    )
    (comp (ref "L_J8")
      (value "JUMP_20X2")
      (footprint "eagle-import:JUMP_20X2")
      (libsource (lib "eagle-import") (part "JUMP_20X2"))
    )
    (comp (ref "L_J9")
      (value "JUMP_20X2")
      (footprint "eagle-import:JUMP_20X2")
      (libsource (lib "eagle-import") (part "JUMP_20X2"))
    )
    (comp (ref "L_J10")
      (value "JUMP_20X2")
      (footprint "eagle-import:JUMP_20X2")
      (libsource (lib "eagle-import") (part "JUMP_20X2"))
    )
    (comp (ref "J12")
      (value "20_HDR_LOCKING_RA")
      (footprint "eagle-import:20_HDR_LOCKING_RA")
      (libsource (lib "eagle-import") (part "20_HDR_LOCKING_RA"))
    )
    (comp (ref "HOLE1")
      (value "3M5_MOUNT_HOLE")
      (footprint "eagle-import:3P5M_HOLE")
      (libsource (lib "eagle-import") (part "3M5_MOUNT_HOLE"))
    )
    (comp (ref "HOLE2")
      (value "3M5_MOUNT_HOLE")
      (footprint "eagle-import:3P5M_HOLE")
      (libsource (lib "eagle-import") (part "3M5_MOUNT_HOLE"))
    )
    (comp (ref "HOLE3")
      (value "3M5_MOUNT_HOLE")
      (footprint "eagle-import:3P5M_HOLE")
      (libsource (lib "eagle-import") (part "3M5_MOUNT_HOLE"))
    )
    (comp (ref "HOLE4")
      (value "3M5_MOUNT_HOLE")
      (footprint "eagle-import:3P5M_HOLE")
      (libsource (lib "eagle-import") (part "3M5_MOUNT_HOLE"))
    )
    (comp (ref "J1")
      (value "20_HDR_LOCKING_RA")
      (footprint "eagle-import:20_HDR_LOCKING_RA")
      (libsource (lib "eagle-import") (part "20_HDR_LOCKING_RA"))
    )
    (comp (ref "J7")
      (value "20_HDR_LOCKING_RA")
      (footprint "eagle-import:20_HDR_LOCKING_RA")
      (libsource (lib "eagle-import") (part "20_HDR_LOCKING_RA"))
    )
    (comp (ref "TP3")
      (value "TEST_LOOP")
      (footprint "eagle-import:TEST_LOOP")
      (libsource (lib "eagle-import") (part "TEST_LOOP"))
    )
    (comp (ref "J9")
      (value "20_HDR_LOCKING_RA")
      (footprint "eagle-import:20_HDR_LOCKING_RA")
      (libsource (lib "eagle-import") (part "20_HDR_LOCKING_RA"))
    )
    (comp (ref "R51")
      (value "10k")
      (footprint "eagle-import:R_P2INCH")
      (libsource (lib "eagle-import") (part "R_P2INCH"))
    )
    (comp (ref "R52")
      (value "10k")
      (footprint "eagle-import:R_P2INCH")
      (libsource (lib "eagle-import") (part "R_P2INCH"))
    )
    (comp (ref "R53")
      (value "10k")
      (footprint "eagle-import:R_P2INCH")
      (libsource (lib "eagle-import") (part "R_P2INCH"))
    )
    (comp (ref "R54")
      (value "10k")
      (footprint "eagle-import:R_P2INCH")
      (libsource (lib "eagle-import") (part "R_P2INCH"))
    )
    (comp (ref "R55")
      (value "10k")
      (footprint "eagle-import:R_P2INCH")
      (libsource (lib "eagle-import") (part "R_P2INCH"))
    )
    (comp (ref "R56")
      (value "10k")
      (footprint "eagle-import:R_P2INCH")
      (libsource (lib "eagle-import") (part "R_P2INCH"))
    )
    (comp (ref "R57")
      (value "10k")
      (footprint "eagle-import:R_P2INCH")
      (libsource (lib "eagle-import") (part "R_P2INCH"))
    )
    (comp (ref "R58")
      (value "10k")
      (footprint "eagle-import:R_P2INCH")
      (libsource (lib "eagle-import") (part "R_P2INCH"))
    )
    (comp (ref "R59")
      (value "10k")
      (footprint "eagle-import:R_P2INCH")
      (libsource (lib "eagle-import") (part "R_P2INCH"))
    )
    (comp (ref "R60")
      (value "10k")
      (footprint "eagle-import:R_P2INCH")
      (libsource (lib "eagle-import") (part "R_P2INCH"))
    )
    (comp (ref "R61")
      (value "10k")
      (footprint "eagle-import:R_P2INCH")
      (libsource (lib "eagle-import") (part "R_P2INCH"))
    )
    (comp (ref "R62")
      (value "10k")
      (footprint "eagle-import:R_P2INCH")
      (libsource (lib "eagle-import") (part "R_P2INCH"))
    )
    (comp (ref "R63")
      (value "10k")
      (footprint "eagle-import:R_P2INCH")
      (libsource (lib "eagle-import") (part "R_P2INCH"))
    )
    (comp (ref "R64")
      (value "10k")
      (footprint "eagle-import:R_P2INCH")
      (libsource (lib "eagle-import") (part "R_P2INCH"))
    )
    (comp (ref "R65")
      (value "10k")
      (footprint "eagle-import:R_P2INCH")
      (libsource (lib "eagle-import") (part "R_P2INCH"))
    )
    (comp (ref "R66")
      (value "10k")
      (footprint "eagle-import:R_P2INCH")
      (libsource (lib "eagle-import") (part "R_P2INCH"))
    )
    (comp (ref "TP11")
      (value "TEST_LOOP")
      (footprint "eagle-import:TEST_LOOP")
      (libsource (lib "eagle-import") (part "TEST_LOOP"))
    )
    (comp (ref "TP12")
      (value "TEST_LOOP")
      (footprint "eagle-import:TEST_LOOP")
      (libsource (lib "eagle-import") (part "TEST_LOOP"))
    )
    (comp (ref "TP13")
      (value "TEST_LOOP")
      (footprint "eagle-import:TEST_LOOP")
      (libsource (lib "eagle-import") (part "TEST_LOOP"))
    )
    (comp (ref "TP14")
      (value "TEST_LOOP")
      (footprint "eagle-import:TEST_LOOP")
      (libsource (lib "eagle-import") (part "TEST_LOOP"))
    )
    (comp (ref "IC6")
      (value "ly62256")
      (footprint "eagle-import:DIP28")
      (libsource (lib "eagle-import") (part "62256"))
    )
    (comp (ref "IC1")
      (value "74ahct245")
      (footprint "eagle-import:DIP20")
      (libsource (lib "eagle-import") (part "74245"))
    )
    (comp (ref "IC2")
      (value "74LVC245")
      (footprint "eagle-import:DIP20")
      (libsource (lib "eagle-import") (part "74245"))
    )
    (comp (ref "IC3")
      (value "74LVC245")
      (footprint "eagle-import:DIP20")
      (libsource (lib "eagle-import") (part "74245"))
    )
    (comp (ref "IC4")
      (value "74LVC245")
      (footprint "eagle-import:DIP20")
      (libsource (lib "eagle-import") (part "74245"))
    )
    (comp (ref "IC5")
      (value "74LVC245")
      (footprint "eagle-import:DIP20")
      (libsource (lib "eagle-import") (part "74245"))
    )
    (comp (ref "R40")
      (value "0")
      (footprint "eagle-import:R_P2INCH")
      (libsource (lib "eagle-import") (part "R_P2INCH"))
    )
    (comp (ref "R41")
      (value "10k")
      (footprint "eagle-import:R_P2INCH")
      (libsource (lib "eagle-import") (part "R_P2INCH"))
    )
    (comp (ref "J3")
      (value "20_HDR_LOCKING_RA")
      (footprint "eagle-import:20_HDR_LOCKING_RA")
      (libsource (lib "eagle-import") (part "20_HDR_LOCKING_RA"))
    )
    (comp (ref "R39")
      (value "10k")
      (footprint "eagle-import:R_P2INCH")
      (libsource (lib "eagle-import") (part "R_P2INCH"))
    )
    (comp (ref "TP2")
      (value "TEST_LOOP")
      (footprint "eagle-import:TEST_LOOP")
      (libsource (lib "eagle-import") (part "TEST_LOOP"))
    )
    (comp (ref "IC8")
      (value "PIC16F1509-E/P")
      (footprint "eagle-import:DIP20")
      (libsource (lib "eagle-import") (part "PIC16F1509-E/P"))
    )
    (comp (ref "J6")
      (value "JUMP_3X1")
      (footprint "eagle-import:JUMP_3X1")
      (libsource (lib "eagle-import") (part "JUMP_3X1"))
    )
    (comp (ref "J22")
      (value "JUMP_6X1")
      (footprint "eagle-import:JUMP_6X1")
      (libsource (lib "eagle-import") (part "JUMP_6X1"))
    )
    (comp (ref "TP10")
      (value "TEST_LOOP")
      (footprint "eagle-import:TEST_LOOP")
      (libsource (lib "eagle-import") (part "TEST_LOOP"))
    )
  )
  (nets
    (net (code "2") (name "+3V3") (class "Default")
      (node (ref "C10") (pin "1") (pinfunction "1_1") (pintype "passive"))
      (node (ref "C11") (pin "2") (pinfunction "2_2") (pintype "passive"))
      (node (ref "C12") (pin "2") (pinfunction "2_2") (pintype "passive"))
      (node (ref "C13") (pin "A") (pinfunction "A_A") (pintype "passive"))
      (node (ref "C4") (pin "1") (pinfunction "1_1") (pintype "passive"))
      (node (ref "C5") (pin "2") (pinfunction "2_2") (pintype "passive"))
      (node (ref "C7") (pin "2") (pinfunction "2_2") (pintype "passive"))
      (node (ref "C8") (pin "1") (pinfunction "1_1") (pintype "passive"))
      (node (ref "IC2") (pin "20") (pinfunction "VCC_20") (pintype "power_in"))
      (node (ref "IC3") (pin "20") (pinfunction "VCC_20") (pintype "power_in"))
      (node (ref "IC4") (pin "20") (pinfunction "VCC_20") (pintype "power_in"))
      (node (ref "IC5") (pin "20") (pinfunction "VCC_20") (pintype "power_in"))
      (node (ref "IC6") (pin "28") (pinfunction "VCC_28") (pintype "power_in"))
      (node (ref "IC8") (pin "1") (pinfunction "VDD_1") (pintype "power_in"))
      (node (ref "J22") (pin "2") (pinfunction "2_2") (pintype "passive"))
      (node (ref "R2") (pin "2") (pinfunction "2_2") (pintype "passive"))
      (node (ref "R39") (pin "2") (pinfunction "2_2") (pintype "passive"))
      (node (ref "R51") (pin "1") (pinfunction "1_1") (pintype "passive"))
      (node (ref "R52") (pin "1") (pinfunction "1_1") (pintype "passive"))
      (node (ref "R53") (pin "1") (pinfunction "1_1") (pintype "passive"))
      (node (ref "R54") (pin "1") (pinfunction "1_1") (pintype "passive"))
      (node (ref "R55") (pin "1") (pinfunction "1_1") (pintype "passive"))
      (node (ref "R56") (pin "1") (pinfunction "1_1") (pintype "passive"))
      (node (ref "R57") (pin "1") (pinfunction "1_1") (pintype "passive"))
      (node (ref "R58") (pin "1") (pinfunction "1_1") (pintype "passive"))
      (node (ref "R59") (pin "1") (pinfunction "1_1") (pintype "passive"))
      (node (ref "R60") (pin "1") (pinfunction "1_1") (pintype "passive"))
      (node (ref "R61") (pin "1") (pinfunction "1_1") (pintype "passive"))
      (node (ref "R62") (pin "1") (pinfunction "1_1") (pintype "passive"))
      (node (ref "R63") (pin "1") (pinfunction "1_1") (pintype "passive"))
      (node (ref "R64") (pin "1") (pinfunction "1_1") (pintype "passive"))
      (node (ref "R65") (pin "1") (pinfunction "1_1") (pintype "passive"))
      (node (ref "R66") (pin "1") (pinfunction "1_1") (pintype "passive"))
      (node (ref "TP7") (pin "P$1") (pinfunction "P$1_P$1") (pintype "bidirectional"))
    )
    (net (code "3") (name "+5V") (class "Default")
      (node (ref "C1") (pin "1") (pinfunction "1_1") (pintype "passive"))
      (node (ref "C14") (pin "A") (pinfunction "A_A") (pintype "passive"))
      (node (ref "C15") (pin "2") (pinfunction "2_2") (pintype "passive"))
      (node (ref "C9") (pin "2") (pinfunction "2_2") (pintype "passive"))
      (node (ref "IC1") (pin "20") (pinfunction "VCC_20") (pintype "power_in"))
      (node (ref "IC7") (pin "20") (pinfunction "VCC_20") (pintype "power_in"))
      (node (ref "J14") (pin "1") (pinfunction "VCC_1") (pintype "power_in"))
      (node (ref "OSC1") (pin "8") (pinfunction "VCC_8") (pintype "power_in"))
      (node (ref "R41") (pin "2") (pinfunction "2_2") (pintype "passive"))
      (node (ref "R5") (pin "2") (pinfunction "2_2") (pintype "passive"))
      (node (ref "TP1") (pin "P$1") (pinfunction "P$1_P$1") (pintype "bidirectional"))
    )
    (net (code "25") (name "3V3_A0") (class "Default")
      (node (ref "IC4") (pin "2") (pinfunction "A1_2") (pintype "bidirectional"))
      (node (ref "IC6") (pin "10") (pinfunction "A0_10") (pintype "input"))
      (node (ref "L_J5") (pin "19") (pinfunction "19_19") (pintype "bidirectional"))
    )
    (net (code "26") (name "3V3_A1") (class "Default")
      (node (ref "IC4") (pin "3") (pinfunction "A2_3") (pintype "bidirectional"))
      (node (ref "IC6") (pin "9") (pinfunction "A1_9") (pintype "input"))
      (node (ref "L_J5") (pin "20") (pinfunction "20_20") (pintype "bidirectional"))
    )
    (net (code "27") (name "3V3_A2") (class "Default")
      (node (ref "IC4") (pin "4") (pinfunction "A3_4") (pintype "bidirectional"))
      (node (ref "IC6") (pin "8") (pinfunction "A2_8") (pintype "input"))
      (node (ref "L_J5") (pin "21") (pinfunction "21_21") (pintype "bidirectional"))
    )
    (net (code "28") (name "3V3_A3") (class "Default")
      (node (ref "IC4") (pin "5") (pinfunction "A4_5") (pintype "bidirectional"))
      (node (ref "IC6") (pin "7") (pinfunction "A3_7") (pintype "input"))
      (node (ref "L_J5") (pin "22") (pinfunction "22_22") (pintype "bidirectional"))
    )
    (net (code "29") (name "3V3_A4") (class "Default")
      (node (ref "IC4") (pin "6") (pinfunction "A5_6") (pintype "bidirectional"))
      (node (ref "IC6") (pin "6") (pinfunction "A4_6") (pintype "input"))
      (node (ref "L_J5") (pin "23") (pinfunction "23_23") (pintype "bidirectional"))
    )
    (net (code "30") (name "3V3_A5") (class "Default")
      (node (ref "IC4") (pin "7") (pinfunction "A6_7") (pintype "bidirectional"))
      (node (ref "IC6") (pin "5") (pinfunction "A5_5") (pintype "input"))
      (node (ref "L_J5") (pin "24") (pinfunction "24_24") (pintype "bidirectional"))
    )
    (net (code "31") (name "3V3_A6") (class "Default")
      (node (ref "IC4") (pin "8") (pinfunction "A7_8") (pintype "bidirectional"))
      (node (ref "IC6") (pin "4") (pinfunction "A6_4") (pintype "input"))
      (node (ref "L_J5") (pin "25") (pinfunction "25_25") (pintype "bidirectional"))
    )
    (net (code "32") (name "3V3_A7") (class "Default")
      (node (ref "IC4") (pin "9") (pinfunction "A8_9") (pintype "bidirectional"))
      (node (ref "IC6") (pin "3") (pinfunction "A7_3") (pintype "input"))
      (node (ref "L_J5") (pin "26") (pinfunction "26_26") (pintype "bidirectional"))
    )
    (net (code "33") (name "3V3_A8") (class "Default")
      (node (ref "IC2") (pin "2") (pinfunction "A1_2") (pintype "bidirectional"))
      (node (ref "IC6") (pin "25") (pinfunction "A8_25") (pintype "input"))
      (node (ref "L_J5") (pin "27") (pinfunction "27_27") (pintype "bidirectional"))
    )
    (net (code "34") (name "3V3_A9") (class "Default")
      (node (ref "IC2") (pin "3") (pinfunction "A2_3") (pintype "bidirectional"))
      (node (ref "IC6") (pin "24") (pinfunction "A9_24") (pintype "input"))
      (node (ref "L_J5") (pin "28") (pinfunction "28_28") (pintype "bidirectional"))
    )
    (net (code "35") (name "3V3_A10") (class "Default")
      (node (ref "IC2") (pin "4") (pinfunction "A3_4") (pintype "bidirectional"))
      (node (ref "IC6") (pin "21") (pinfunction "A10_21") (pintype "input"))
      (node (ref "L_J5") (pin "29") (pinfunction "29_29") (pintype "bidirectional"))
    )
    (net (code "36") (name "3V3_A11") (class "Default")
      (node (ref "IC2") (pin "5") (pinfunction "A4_5") (pintype "bidirectional"))
      (node (ref "IC6") (pin "23") (pinfunction "A11_23") (pintype "input"))
      (node (ref "L_J5") (pin "30") (pinfunction "30_30") (pintype "bidirectional"))
    )
    (net (code "37") (name "3V3_A12") (class "Default")
      (node (ref "IC2") (pin "6") (pinfunction "A5_6") (pintype "bidirectional"))
      (node (ref "IC6") (pin "2") (pinfunction "A12_2") (pintype "input"))
      (node (ref "L_J5") (pin "31") (pinfunction "31_31") (pintype "bidirectional"))
    )
    (net (code "38") (name "3V3_A13") (class "Default")
      (node (ref "IC2") (pin "7") (pinfunction "A6_7") (pintype "bidirectional"))
      (node (ref "IC6") (pin "26") (pinfunction "A13_26") (pintype "input"))
      (node (ref "L_J5") (pin "38") (pinfunction "38_38") (pintype "bidirectional"))
    )
    (net (code "39") (name "3V3_A14") (class "Default")
      (node (ref "IC2") (pin "8") (pinfunction "A7_8") (pintype "bidirectional"))
      (node (ref "IC6") (pin "1") (pinfunction "A14_1") (pintype "input"))
      (node (ref "L_J5") (pin "39") (pinfunction "39_39") (pintype "bidirectional"))
    )
    (net (code "40") (name "3V3_A15") (class "Default")
      (node (ref "IC2") (pin "9") (pinfunction "A8_9") (pintype "bidirectional"))
      (node (ref "L_J5") (pin "40") (pinfunction "40_40") (pintype "bidirectional"))
    )
    (net (code "41") (name "3V3_CK2") (class "Default")
      (node (ref "IC3") (pin "18") (pinfunction "B1_18") (pintype "bidirectional"))
      (node (ref "L_J7") (pin "34") (pinfunction "34_34") (pintype "bidirectional"))
    )
    (net (code "42") (name "3V3_CS_N") (class "Default")
      (node (ref "IC3") (pin "16") (pinfunction "B3_16") (pintype "bidirectional"))
      (node (ref "L_J7") (pin "33") (pinfunction "33_33") (pintype "bidirectional"))
    )
    (net (code "43") (name "3V3_D0") (class "Default")
      (node (ref "IC6") (pin "11") (pinfunction "D0_11") (pintype "bidirectional"))
      (node (ref "L_J7") (pin "5") (pinfunction "5_5") (pintype "bidirectional"))
    )
    (net (code "44") (name "3V3_D1") (class "Default")
      (node (ref "IC6") (pin "12") (pinfunction "D1_12") (pintype "bidirectional"))
      (node (ref "L_J7") (pin "7") (pinfunction "7_7") (pintype "bidirectional"))
    )
    (net (code "45") (name "3V3_D2") (class "Default")
      (node (ref "IC6") (pin "13") (pinfunction "D2_13") (pintype "bidirectional"))
      (node (ref "L_J7") (pin "9") (pinfunction "9_9") (pintype "bidirectional"))
    )
    (net (code "46") (name "3V3_D3") (class "Default")
      (node (ref "IC6") (pin "15") (pinfunction "D3_15") (pintype "bidirectional"))
      (node (ref "L_J7") (pin "11") (pinfunction "11_11") (pintype "bidirectional"))
    )
    (net (code "47") (name "3V3_D4") (class "Default")
      (node (ref "IC6") (pin "16") (pinfunction "D4_16") (pintype "bidirectional"))
      (node (ref "L_J7") (pin "13") (pinfunction "13_13") (pintype "bidirectional"))
    )
    (net (code "48") (name "3V3_D5") (class "Default")
      (node (ref "IC6") (pin "17") (pinfunction "D5_17") (pintype "bidirectional"))
      (node (ref "L_J7") (pin "15") (pinfunction "15_15") (pintype "bidirectional"))
    )
    (net (code "49") (name "3V3_D6") (class "Default")
      (node (ref "IC6") (pin "18") (pinfunction "D6_18") (pintype "bidirectional"))
      (node (ref "L_J7") (pin "17") (pinfunction "17_17") (pintype "bidirectional"))
    )
    (net (code "50") (name "3V3_D7") (class "Default")
      (node (ref "IC6") (pin "19") (pinfunction "D7_19") (pintype "bidirectional"))
      (node (ref "L_J7") (pin "19") (pinfunction "19_19") (pintype "bidirectional"))
    )
    (net (code "51") (name "3V3_RD0") (class "Default")
      (node (ref "IC1") (pin "2") (pinfunction "A1_2") (pintype "bidirectional"))
      (node (ref "L_J5") (pin "3") (pinfunction "3_3") (pintype "bidirectional"))
    )
    (net (code "52") (name "3V3_RD1") (class "Default")
      (node (ref "IC1") (pin "3") (pinfunction "A2_3") (pintype "bidirectional"))
      (node (ref "L_J5") (pin "4") (pinfunction "4_4") (pintype "bidirectional"))
    )
    (net (code "53") (name "3V3_RD2") (class "Default")
      (node (ref "IC1") (pin "4") (pinfunction "A3_4") (pintype "bidirectional"))
      (node (ref "L_J5") (pin "5") (pinfunction "5_5") (pintype "bidirectional"))
    )
    (net (code "54") (name "3V3_RD3") (class "Default")
      (node (ref "IC1") (pin "5") (pinfunction "A4_5") (pintype "bidirectional"))
      (node (ref "L_J5") (pin "6") (pinfunction "6_6") (pintype "bidirectional"))
    )
    (net (code "55") (name "3V3_RD4") (class "Default")
      (node (ref "IC1") (pin "6") (pinfunction "A5_6") (pintype "bidirectional"))
      (node (ref "L_J5") (pin "7") (pinfunction "7_7") (pintype "bidirectional"))
    )
    (net (code "56") (name "3V3_RD5") (class "Default")
      (node (ref "IC1") (pin "7") (pinfunction "A6_7") (pintype "bidirectional"))
      (node (ref "L_J5") (pin "8") (pinfunction "8_8") (pintype "bidirectional"))
    )
    (net (code "57") (name "3V3_RD6") (class "Default")
      (node (ref "IC1") (pin "8") (pinfunction "A7_8") (pintype "bidirectional"))
      (node (ref "L_J5") (pin "9") (pinfunction "9_9") (pintype "bidirectional"))
    )
    (net (code "58") (name "3V3_RD7") (class "Default")
      (node (ref "IC1") (pin "9") (pinfunction "A8_9") (pintype "bidirectional"))
      (node (ref "L_J5") (pin "10") (pinfunction "10_10") (pintype "bidirectional"))
    )
    (net (code "59") (name "3V3_WD0") (class "Default")
      (node (ref "IC5") (pin "2") (pinfunction "A1_2") (pintype "bidirectional"))
      (node (ref "L_J5") (pin "11") (pinfunction "11_11") (pintype "bidirectional"))
    )
    (net (code "60") (name "3V3_WD1") (class "Default")
      (node (ref "IC5") (pin "3") (pinfunction "A2_3") (pintype "bidirectional"))
      (node (ref "L_J5") (pin "12") (pinfunction "12_12") (pintype "bidirectional"))
    )
    (net (code "61") (name "3V3_WD2") (class "Default")
      (node (ref "IC5") (pin "4") (pinfunction "A3_4") (pintype "bidirectional"))
      (node (ref "L_J5") (pin "13") (pinfunction "13_13") (pintype "bidirectional"))
    )
    (net (code "62") (name "3V3_WD3") (class "Default")
      (node (ref "IC5") (pin "5") (pinfunction "A4_5") (pintype "bidirectional"))
      (node (ref "L_J5") (pin "14") (pinfunction "14_14") (pintype "bidirectional"))
    )
    (net (code "63") (name "3V3_WD4") (class "Default")
      (node (ref "IC5") (pin "6") (pinfunction "A5_6") (pintype "bidirectional"))
      (node (ref "L_J5") (pin "15") (pinfunction "15_15") (pintype "bidirectional"))
    )
    (net (code "64") (name "3V3_WD5") (class "Default")
      (node (ref "IC5") (pin "7") (pinfunction "A6_7") (pintype "bidirectional"))
      (node (ref "L_J5") (pin "16") (pinfunction "16_16") (pintype "bidirectional"))
    )
    (net (code "65") (name "3V3_WD6") (class "Default")
      (node (ref "IC5") (pin "8") (pinfunction "A7_8") (pintype "bidirectional"))
      (node (ref "L_J5") (pin "17") (pinfunction "17_17") (pintype "bidirectional"))
    )
    (net (code "66") (name "3V3_WD7") (class "Default")
      (node (ref "IC5") (pin "9") (pinfunction "A8_9") (pintype "bidirectional"))
      (node (ref "L_J5") (pin "18") (pinfunction "18_18") (pintype "bidirectional"))
    )
    (net (code "67") (name "3V3_WRITE_N") (class "Default")
      (node (ref "IC3") (pin "17") (pinfunction "B2_17") (pintype "bidirectional"))
      (node (ref "L_J7") (pin "32") (pinfunction "32_32") (pintype "bidirectional"))
    )
    (net (code "68") (name "A0") (class "Default")
      (node (ref "IC4") (pin "18") (pinfunction "B1_18") (pintype "bidirectional"))
      (node (ref "J1") (pin "5") (pinfunction "5_5") (pintype "bidirectional"))
    )
    (net (code "69") (name "A1") (class "Default")
      (node (ref "IC4") (pin "17") (pinfunction "B2_17") (pintype "bidirectional"))
      (node (ref "J1") (pin "6") (pinfunction "6_6") (pintype "bidirectional"))
    )
    (net (code "70") (name "A2") (class "Default")
      (node (ref "IC4") (pin "16") (pinfunction "B3_16") (pintype "bidirectional"))
      (node (ref "J1") (pin "7") (pinfunction "7_7") (pintype "bidirectional"))
    )
    (net (code "71") (name "A3") (class "Default")
      (node (ref "IC4") (pin "15") (pinfunction "B4_15") (pintype "bidirectional"))
      (node (ref "J1") (pin "8") (pinfunction "8_8") (pintype "bidirectional"))
    )
    (net (code "72") (name "A4") (class "Default")
      (node (ref "IC4") (pin "14") (pinfunction "B5_14") (pintype "bidirectional"))
      (node (ref "J1") (pin "9") (pinfunction "9_9") (pintype "bidirectional"))
    )
    (net (code "73") (name "A5") (class "Default")
      (node (ref "IC4") (pin "13") (pinfunction "B6_13") (pintype "bidirectional"))
      (node (ref "J1") (pin "10") (pinfunction "10_10") (pintype "bidirectional"))
    )
    (net (code "74") (name "A6") (class "Default")
      (node (ref "IC4") (pin "12") (pinfunction "B7_12") (pintype "bidirectional"))
      (node (ref "J1") (pin "11") (pinfunction "11_11") (pintype "bidirectional"))
    )
    (net (code "75") (name "A7") (class "Default")
      (node (ref "IC4") (pin "11") (pinfunction "B8_11") (pintype "bidirectional"))
      (node (ref "J1") (pin "12") (pinfunction "12_12") (pintype "bidirectional"))
    )
    (net (code "76") (name "A8") (class "Default")
      (node (ref "IC2") (pin "18") (pinfunction "B1_18") (pintype "bidirectional"))
      (node (ref "J1") (pin "13") (pinfunction "13_13") (pintype "bidirectional"))
    )
    (net (code "77") (name "A9") (class "Default")
      (node (ref "IC2") (pin "17") (pinfunction "B2_17") (pintype "bidirectional"))
      (node (ref "J1") (pin "14") (pinfunction "14_14") (pintype "bidirectional"))
    )
    (net (code "78") (name "A10") (class "Default")
      (node (ref "IC2") (pin "16") (pinfunction "B3_16") (pintype "bidirectional"))
      (node (ref "J1") (pin "15") (pinfunction "15_15") (pintype "bidirectional"))
    )
    (net (code "79") (name "A11") (class "Default")
      (node (ref "IC2") (pin "15") (pinfunction "B4_15") (pintype "bidirectional"))
      (node (ref "J1") (pin "16") (pinfunction "16_16") (pintype "bidirectional"))
    )
    (net (code "80") (name "A12") (class "Default")
      (node (ref "IC2") (pin "14") (pinfunction "B5_14") (pintype "bidirectional"))
      (node (ref "J1") (pin "17") (pinfunction "17_17") (pintype "bidirectional"))
    )
    (net (code "81") (name "A13") (class "Default")
      (node (ref "IC2") (pin "13") (pinfunction "B6_13") (pintype "bidirectional"))
      (node (ref "J1") (pin "18") (pinfunction "18_18") (pintype "bidirectional"))
    )
    (net (code "82") (name "A14") (class "Default")
      (node (ref "IC2") (pin "12") (pinfunction "B7_12") (pintype "bidirectional"))
      (node (ref "J1") (pin "19") (pinfunction "19_19") (pintype "bidirectional"))
    )
    (net (code "83") (name "A15") (class "Default")
      (node (ref "IC2") (pin "11") (pinfunction "B8_11") (pintype "bidirectional"))
      (node (ref "J1") (pin "20") (pinfunction "20_20") (pintype "bidirectional"))
    )
    (net (code "84") (name "ACTIVE_PHASE") (class "Default")
      (node (ref "IC7") (pin "9") (pinfunction "A8_9") (pintype "bidirectional"))
      (node (ref "L_J10") (pin "40") (pinfunction "40_40") (pintype "bidirectional"))
    )
    (net (code "85") (name "ACTIVE_PHASE_3V3") (class "Default")
      (node (ref "IC7") (pin "11") (pinfunction "B8_11") (pintype "bidirectional"))
      (node (ref "J2") (pin "1") (pinfunction "1_1") (pintype "passive"))
    )
    (net (code "86") (name "CK1_OUT") (class "Default")
      (node (ref "IC7") (pin "7") (pinfunction "A6_7") (pintype "bidirectional"))
      (node (ref "L_J10") (pin "37") (pinfunction "37_37") (pintype "bidirectional"))
    )
    (net (code "87") (name "CK1_OUT_3V3") (class "Default")
      (node (ref "IC7") (pin "13") (pinfunction "B6_13") (pintype "bidirectional"))
      (node (ref "J2") (pin "3") (pinfunction "3_3") (pintype "passive"))
    )
    (net (code "88") (name "CK2_IN") (class "Default")
      (node (ref "IC3") (pin "2") (pinfunction "A1_2") (pintype "bidirectional"))
      (node (ref "TP3") (pin "P$1") (pinfunction "P$1_P$1") (pintype "bidirectional"))
    )
    (net (code "89") (name "CK2_OUT") (class "Default")
      (node (ref "IC7") (pin "8") (pinfunction "A7_8") (pintype "bidirectional"))
      (node (ref "L_J10") (pin "38") (pinfunction "38_38") (pintype "bidirectional"))
    )
    (net (code "90") (name "CK2_OUT_3V3") (class "Default")
      (node (ref "IC7") (pin "12") (pinfunction "B7_12") (pintype "bidirectional"))
      (node (ref "J2") (pin "2") (pinfunction "2_2") (pintype "passive"))
    )
    (net (code "91") (name "CLK_3V") (class "Default")
      (node (ref "L_J9") (pin "11") (pinfunction "11_11") (pintype "bidirectional"))
      (node (ref "Q1") (pin "D") (pinfunction "D_D") (pintype "passive"))
      (node (ref "R2") (pin "1") (pinfunction "1_1") (pintype "passive"))
    )
    (net (code "92") (name "CLK_5V") (class "Default")
      (node (ref "Q1") (pin "G") (pinfunction "G_G") (pintype "passive"))
      (node (ref "R1") (pin "1") (pinfunction "1_1") (pintype "passive"))
      (node (ref "R3") (pin "2") (pinfunction "2_2") (pintype "passive"))
    )
    (net (code "93") (name "COUNT0_CLK") (class "Default")
      (node (ref "IC7") (pin "2") (pinfunction "A1_2") (pintype "bidirectional"))
      (node (ref "L_J7") (pin "35") (pinfunction "35_35") (pintype "bidirectional"))
    )
    (net (code "94") (name "COUNT0_CLK_DRV") (class "Default")
      (node (ref "IC7") (pin "18") (pinfunction "B1_18") (pintype "bidirectional"))
      (node (ref "J4") (pin "3") (pinfunction "3_3") (pintype "passive"))
    )
    (net (code "95") (name "COUNT0_DATA") (class "Default")
      (node (ref "IC7") (pin "3") (pinfunction "A2_3") (pintype "bidirectional"))
      (node (ref "L_J7") (pin "36") (pinfunction "36_36") (pintype "bidirectional"))
    )
    (net (code "96") (name "COUNT0_DATA_DRV") (class "Default")
      (node (ref "IC7") (pin "17") (pinfunction "B2_17") (pintype "bidirectional"))
      (node (ref "J4") (pin "1") (pinfunction "1_1") (pintype "passive"))
    )
    (net (code "97") (name "COUNT1_CLK") (class "Default")
      (node (ref "IC7") (pin "4") (pinfunction "A3_4") (pintype "bidirectional"))
      (node (ref "L_J7") (pin "37") (pinfunction "37_37") (pintype "bidirectional"))
    )
    (net (code "98") (name "COUNT1_CLK_DRV") (class "Default")
      (node (ref "IC7") (pin "16") (pinfunction "B3_16") (pintype "bidirectional"))
      (node (ref "J5") (pin "3") (pinfunction "3_3") (pintype "passive"))
    )
    (net (code "99") (name "COUNT1_DATA") (class "Default")
      (node (ref "IC7") (pin "5") (pinfunction "A4_5") (pintype "bidirectional"))
      (node (ref "L_J7") (pin "38") (pinfunction "38_38") (pintype "bidirectional"))
    )
    (net (code "100") (name "COUNT1_DATA_DRV") (class "Default")
      (node (ref "IC7") (pin "15") (pinfunction "B4_15") (pintype "bidirectional"))
      (node (ref "J5") (pin "1") (pinfunction "1_1") (pintype "passive"))
    )
    (net (code "101") (name "CS_N") (class "Default")
      (node (ref "IC3") (pin "4") (pinfunction "A3_4") (pintype "bidirectional"))
      (node (ref "J1") (pin "1") (pinfunction "1_1") (pintype "bidirectional"))
    )
    (net (code "102") (name "GND") (class "Default")
      (node (ref "C1") (pin "2") (pinfunction "2_2") (pintype "passive"))
      (node (ref "C10") (pin "2") (pinfunction "2_2") (pintype "passive"))
      (node (ref "C11") (pin "1") (pinfunction "1_1") (pintype "passive"))
      (node (ref "C12") (pin "1") (pinfunction "1_1") (pintype "passive"))
      (node (ref "C13") (pin "K") (pinfunction "K_K") (pintype "passive"))
      (node (ref "C14") (pin "K") (pinfunction "K_K") (pintype "passive"))
      (node (ref "C15") (pin "1") (pinfunction "1_1") (pintype "passive"))
      (node (ref "C4") (pin "2") (pinfunction "2_2") (pintype "passive"))
      (node (ref "C5") (pin "1") (pinfunction "1_1") (pintype "passive"))
      (node (ref "C7") (pin "1") (pinfunction "1_1") (pintype "passive"))
      (node (ref "C8") (pin "2") (pinfunction "2_2") (pintype "passive"))
      (node (ref "C9") (pin "1") (pinfunction "1_1") (pintype "passive"))
      (node (ref "IC1") (pin "10") (pinfunction "GND_10") (pintype "power_in"))
      (node (ref "IC1") (pin "19") (pinfunction "G_19") (pintype "input"))
      (node (ref "IC2") (pin "10") (pinfunction "GND_10") (pintype "power_in"))
      (node (ref "IC3") (pin "10") (pinfunction "GND_10") (pintype "power_in"))
      (node (ref "IC3") (pin "19") (pinfunction "G_19") (pintype "input"))
      (node (ref "IC3") (pin "5") (pinfunction "A4_5") (pintype "bidirectional"))
      (node (ref "IC3") (pin "6") (pinfunction "A5_6") (pintype "bidirectional"))
      (node (ref "IC3") (pin "7") (pinfunction "A6_7") (pintype "bidirectional"))
      (node (ref "IC3") (pin "8") (pinfunction "A7_8") (pintype "bidirectional"))
      (node (ref "IC3") (pin "9") (pinfunction "A8_9") (pintype "bidirectional"))
      (node (ref "IC4") (pin "10") (pinfunction "GND_10") (pintype "power_in"))
      (node (ref "IC5") (pin "10") (pinfunction "GND_10") (pintype "power_in"))
      (node (ref "IC5") (pin "19") (pinfunction "G_19") (pintype "input"))
      (node (ref "IC6") (pin "14") (pinfunction "GND_14") (pintype "power_in"))
      (node (ref "IC7") (pin "10") (pinfunction "GND_10") (pintype "power_in"))
      (node (ref "IC7") (pin "19") (pinfunction "G_19") (pintype "input"))
      (node (ref "IC8") (pin "20") (pinfunction "VSS_20") (pintype "passive"))
      (node (ref "J1") (pin "2") (pinfunction "2_2") (pintype "bidirectional"))
      (node (ref "J1") (pin "4") (pinfunction "4_4") (pintype "bidirectional"))
      (node (ref "J11") (pin "1") (pinfunction "1_1") (pintype "bidirectional"))
      (node (ref "J11") (pin "10") (pinfunction "10_10") (pintype "bidirectional"))
      (node (ref "J11") (pin "11") (pinfunction "11_11") (pintype "bidirectional"))
      (node (ref "J11") (pin "20") (pinfunction "20_20") (pintype "bidirectional"))
      (node (ref "J12") (pin "1") (pinfunction "1_1") (pintype "bidirectional"))
      (node (ref "J12") (pin "10") (pinfunction "10_10") (pintype "bidirectional"))
      (node (ref "J12") (pin "11") (pinfunction "11_11") (pintype "bidirectional"))
      (node (ref "J12") (pin "12") (pinfunction "12_12") (pintype "bidirectional"))
      (node (ref "J12") (pin "13") (pinfunction "13_13") (pintype "bidirectional"))
      (node (ref "J12") (pin "14") (pinfunction "14_14") (pintype "bidirectional"))
      (node (ref "J12") (pin "15") (pinfunction "15_15") (pintype "bidirectional"))
      (node (ref "J12") (pin "16") (pinfunction "16_16") (pintype "bidirectional"))
      (node (ref "J12") (pin "17") (pinfunction "17_17") (pintype "bidirectional"))
      (node (ref "J12") (pin "18") (pinfunction "18_18") (pintype "bidirectional"))
      (node (ref "J12") (pin "19") (pinfunction "19_19") (pintype "bidirectional"))
      (node (ref "J12") (pin "20") (pinfunction "20_20") (pintype "bidirectional"))
      (node (ref "J14") (pin "4") (pinfunction "GND_4") (pintype "power_in"))
      (node (ref "J22") (pin "3") (pinfunction "3_3") (pintype "passive"))
      (node (ref "J3") (pin "1") (pinfunction "1_1") (pintype "bidirectional"))
      (node (ref "J3") (pin "10") (pinfunction "10_10") (pintype "bidirectional"))
      (node (ref "J3") (pin "11") (pinfunction "11_11") (pintype "bidirectional"))
      (node (ref "J3") (pin "12") (pinfunction "12_12") (pintype "bidirectional"))
      (node (ref "J3") (pin "13") (pinfunction "13_13") (pintype "bidirectional"))
      (node (ref "J3") (pin "14") (pinfunction "14_14") (pintype "bidirectional"))
      (node (ref "J3") (pin "15") (pinfunction "15_15") (pintype "bidirectional"))
      (node (ref "J3") (pin "16") (pinfunction "16_16") (pintype "bidirectional"))
      (node (ref "J3") (pin "17") (pinfunction "17_17") (pintype "bidirectional"))
      (node (ref "J3") (pin "18") (pinfunction "18_18") (pintype "bidirectional"))
      (node (ref "J3") (pin "19") (pinfunction "19_19") (pintype "bidirectional"))
      (node (ref "J3") (pin "20") (pinfunction "20_20") (pintype "bidirectional"))
      (node (ref "J4") (pin "2") (pinfunction "2_2") (pintype "passive"))
      (node (ref "J5") (pin "2") (pinfunction "2_2") (pintype "passive"))
      (node (ref "J6") (pin "2") (pinfunction "2_2") (pintype "passive"))
      (node (ref "J7") (pin "1") (pinfunction "1_1") (pintype "bidirectional"))
      (node (ref "J7") (pin "10") (pinfunction "10_10") (pintype "bidirectional"))
      (node (ref "J7") (pin "11") (pinfunction "11_11") (pintype "bidirectional"))
      (node (ref "J7") (pin "20") (pinfunction "20_20") (pintype "bidirectional"))
      (node (ref "J9") (pin "1") (pinfunction "1_1") (pintype "bidirectional"))
      (node (ref "J9") (pin "10") (pinfunction "10_10") (pintype "bidirectional"))
      (node (ref "J9") (pin "11") (pinfunction "11_11") (pintype "bidirectional"))
      (node (ref "J9") (pin "20") (pinfunction "20_20") (pintype "bidirectional"))
      (node (ref "L_J4") (pin "10") (pinfunction "10_10") (pintype "bidirectional"))
      (node (ref "L_J4") (pin "12") (pinfunction "12_12") (pintype "bidirectional"))
      (node (ref "L_J4") (pin "14") (pinfunction "14_14") (pintype "bidirectional"))
      (node (ref "L_J4") (pin "16") (pinfunction "16_16") (pintype "bidirectional"))
      (node (ref "L_J4") (pin "18") (pinfunction "18_18") (pintype "bidirectional"))
      (node (ref "L_J4") (pin "2") (pinfunction "2_2") (pintype "bidirectional"))
      (node (ref "L_J4") (pin "20") (pinfunction "20_20") (pintype "bidirectional"))
      (node (ref "L_J4") (pin "22") (pinfunction "22_22") (pintype "bidirectional"))
      (node (ref "L_J4") (pin "24") (pinfunction "24_24") (pintype "bidirectional"))
      (node (ref "L_J4") (pin "4") (pinfunction "4_4") (pintype "bidirectional"))
      (node (ref "L_J4") (pin "6") (pinfunction "6_6") (pintype "bidirectional"))
      (node (ref "L_J4") (pin "8") (pinfunction "8_8") (pintype "bidirectional"))
      (node (ref "L_J7") (pin "10") (pinfunction "10_10") (pintype "bidirectional"))
      (node (ref "L_J7") (pin "12") (pinfunction "12_12") (pintype "bidirectional"))
      (node (ref "L_J7") (pin "14") (pinfunction "14_14") (pintype "bidirectional"))
      (node (ref "L_J7") (pin "16") (pinfunction "16_16") (pintype "bidirectional"))
      (node (ref "L_J7") (pin "18") (pinfunction "18_18") (pintype "bidirectional"))
      (node (ref "L_J7") (pin "2") (pinfunction "2_2") (pintype "bidirectional"))
      (node (ref "L_J7") (pin "20") (pinfunction "20_20") (pintype "bidirectional"))
      (node (ref "L_J7") (pin "22") (pinfunction "22_22") (pintype "bidirectional"))
      (node (ref "L_J7") (pin "24") (pinfunction "24_24") (pintype "bidirectional"))
      (node (ref "L_J7") (pin "4") (pinfunction "4_4") (pintype "bidirectional"))
      (node (ref "L_J7") (pin "6") (pinfunction "6_6") (pintype "bidirectional"))
      (node (ref "L_J7") (pin "8") (pinfunction "8_8") (pintype "bidirectional"))
      (node (ref "OSC1") (pin "4") (pinfunction "GND_4") (pintype "power_in"))
      (node (ref "Q1") (pin "S") (pinfunction "S_S") (pintype "passive"))
      (node (ref "R3") (pin "1") (pinfunction "1_1") (pintype "passive"))
      (node (ref "R40") (pin "2") (pinfunction "2_2") (pintype "passive"))
      (node (ref "TP15") (pin "P$1") (pinfunction "P$1_P$1") (pintype "bidirectional"))
      (node (ref "TP8") (pin "P$1") (pinfunction "P$1_P$1") (pintype "bidirectional"))
    )
    (net (code "103") (name "INT_MASK_0") (class "Default")
      (node (ref "J12") (pin "2") (pinfunction "2_2") (pintype "bidirectional"))
      (node (ref "L_J4") (pin "26") (pinfunction "26_26") (pintype "bidirectional"))
    )
    (net (code "104") (name "INT_MASK_1") (class "Default")
      (node (ref "J12") (pin "3") (pinfunction "3_3") (pintype "bidirectional"))
      (node (ref "L_J4") (pin "23") (pinfunction "23_23") (pintype "bidirectional"))
    )
    (net (code "105") (name "INT_MASK_2") (class "Default")
      (node (ref "J12") (pin "4") (pinfunction "4_4") (pintype "bidirectional"))
      (node (ref "L_J4") (pin "21") (pinfunction "21_21") (pintype "bidirectional"))
    )
    (net (code "106") (name "INT_MASK_3") (class "Default")
      (node (ref "J12") (pin "5") (pinfunction "5_5") (pintype "bidirectional"))
      (node (ref "L_J4") (pin "19") (pinfunction "19_19") (pintype "bidirectional"))
    )
    (net (code "107") (name "INT_MASK_4") (class "Default")
      (node (ref "J12") (pin "6") (pinfunction "6_6") (pintype "bidirectional"))
      (node (ref "L_J4") (pin "17") (pinfunction "17_17") (pintype "bidirectional"))
    )
    (net (code "108") (name "INT_MASK_5") (class "Default")
      (node (ref "J12") (pin "7") (pinfunction "7_7") (pintype "bidirectional"))
      (node (ref "L_J4") (pin "15") (pinfunction "15_15") (pintype "bidirectional"))
    )
    (net (code "109") (name "INT_MASK_6") (class "Default")
      (node (ref "J12") (pin "8") (pinfunction "8_8") (pintype "bidirectional"))
      (node (ref "L_J4") (pin "13") (pinfunction "13_13") (pintype "bidirectional"))
    )
    (net (code "110") (name "INT_MASK_7") (class "Default")
      (node (ref "J12") (pin "9") (pinfunction "9_9") (pintype "bidirectional"))
      (node (ref "L_J4") (pin "11") (pinfunction "11_11") (pintype "bidirectional"))
    )
    (net (code "111") (name "INT_STATUS_0") (class "Default")
      (node (ref "J3") (pin "2") (pinfunction "2_2") (pintype "bidirectional"))
      (node (ref "L_J4") (pin "36") (pinfunction "36_36") (pintype "bidirectional"))
    )
    (net (code "112") (name "INT_STATUS_1") (class "Default")
      (node (ref "J3") (pin "3") (pinfunction "3_3") (pintype "bidirectional"))
      (node (ref "L_J4") (pin "35") (pinfunction "35_35") (pintype "bidirectional"))
    )
    (net (code "113") (name "INT_STATUS_2") (class "Default")
      (node (ref "J3") (pin "4") (pinfunction "4_4") (pintype "bidirectional"))
      (node (ref "L_J4") (pin "34") (pinfunction "34_34") (pintype "bidirectional"))
    )
    (net (code "114") (name "INT_STATUS_3") (class "Default")
      (node (ref "J3") (pin "5") (pinfunction "5_5") (pintype "bidirectional"))
      (node (ref "L_J4") (pin "33") (pinfunction "33_33") (pintype "bidirectional"))
    )
    (net (code "115") (name "INT_STATUS_4") (class "Default")
      (node (ref "J3") (pin "6") (pinfunction "6_6") (pintype "bidirectional"))
      (node (ref "L_J4") (pin "32") (pinfunction "32_32") (pintype "bidirectional"))
    )
    (net (code "116") (name "INT_STATUS_5") (class "Default")
      (node (ref "J3") (pin "7") (pinfunction "7_7") (pintype "bidirectional"))
      (node (ref "L_J4") (pin "31") (pinfunction "31_31") (pintype "bidirectional"))
    )
    (net (code "117") (name "INT_STATUS_6") (class "Default")
      (node (ref "J3") (pin "8") (pinfunction "8_8") (pintype "bidirectional"))
      (node (ref "L_J4") (pin "30") (pinfunction "30_30") (pintype "bidirectional"))
    )
    (net (code "118") (name "INT_STATUS_7") (class "Default")
      (node (ref "J3") (pin "9") (pinfunction "9_9") (pintype "bidirectional"))
      (node (ref "L_J4") (pin "29") (pinfunction "29_29") (pintype "bidirectional"))
    )
    (net (code "119") (name "IN_0") (class "Default")
      (node (ref "J9") (pin "2") (pinfunction "2_2") (pintype "bidirectional"))
      (node (ref "L_J10") (pin "19") (pinfunction "19_19") (pintype "bidirectional"))
      (node (ref "R66") (pin "2") (pinfunction "2_2") (pintype "passive"))
      (node (ref "TP11") (pin "P$1") (pinfunction "P$1_P$1") (pintype "bidirectional"))
    )
    (net (code "120") (name "IN_1") (class "Default")
      (node (ref "J9") (pin "3") (pinfunction "3_3") (pintype "bidirectional"))
      (node (ref "L_J10") (pin "20") (pinfunction "20_20") (pintype "bidirectional"))
      (node (ref "R65") (pin "2") (pinfunction "2_2") (pintype "passive"))
      (node (ref "TP12") (pin "P$1") (pinfunction "P$1_P$1") (pintype "bidirectional"))
    )
    (net (code "121") (name "IN_2") (class "Default")
      (node (ref "J9") (pin "4") (pinfunction "4_4") (pintype "bidirectional"))
      (node (ref "L_J10") (pin "21") (pinfunction "21_21") (pintype "bidirectional"))
      (node (ref "R64") (pin "2") (pinfunction "2_2") (pintype "passive"))
      (node (ref "TP13") (pin "P$1") (pinfunction "P$1_P$1") (pintype "bidirectional"))
    )
    (net (code "122") (name "IN_3") (class "Default")
      (node (ref "J9") (pin "5") (pinfunction "5_5") (pintype "bidirectional"))
      (node (ref "L_J10") (pin "22") (pinfunction "22_22") (pintype "bidirectional"))
      (node (ref "R63") (pin "2") (pinfunction "2_2") (pintype "passive"))
      (node (ref "TP14") (pin "P$1") (pinfunction "P$1_P$1") (pintype "bidirectional"))
    )
    (net (code "123") (name "IN_4") (class "Default")
      (node (ref "J9") (pin "6") (pinfunction "6_6") (pintype "bidirectional"))
      (node (ref "L_J10") (pin "23") (pinfunction "23_23") (pintype "bidirectional"))
      (node (ref "R62") (pin "2") (pinfunction "2_2") (pintype "passive"))
    )
    (net (code "124") (name "IN_5") (class "Default")
      (node (ref "J9") (pin "7") (pinfunction "7_7") (pintype "bidirectional"))
      (node (ref "L_J10") (pin "24") (pinfunction "24_24") (pintype "bidirectional"))
      (node (ref "R61") (pin "2") (pinfunction "2_2") (pintype "passive"))
    )
    (net (code "125") (name "IN_6") (class "Default")
      (node (ref "J9") (pin "8") (pinfunction "8_8") (pintype "bidirectional"))
      (node (ref "L_J10") (pin "25") (pinfunction "25_25") (pintype "bidirectional"))
      (node (ref "R60") (pin "2") (pinfunction "2_2") (pintype "passive"))
    )
    (net (code "126") (name "IN_7") (class "Default")
      (node (ref "J9") (pin "9") (pinfunction "9_9") (pintype "bidirectional"))
      (node (ref "L_J10") (pin "26") (pinfunction "26_26") (pintype "bidirectional"))
      (node (ref "R59") (pin "2") (pinfunction "2_2") (pintype "passive"))
    )
    (net (code "127") (name "IN_8") (class "Default")
      (node (ref "J9") (pin "12") (pinfunction "12_12") (pintype "bidirectional"))
      (node (ref "L_J10") (pin "27") (pinfunction "27_27") (pintype "bidirectional"))
      (node (ref "R58") (pin "2") (pinfunction "2_2") (pintype "passive"))
    )
    (net (code "128") (name "IN_9") (class "Default")
      (node (ref "J9") (pin "13") (pinfunction "13_13") (pintype "bidirectional"))
      (node (ref "L_J10") (pin "28") (pinfunction "28_28") (pintype "bidirectional"))
      (node (ref "R57") (pin "2") (pinfunction "2_2") (pintype "passive"))
    )
    (net (code "129") (name "IN_10") (class "Default")
      (node (ref "J9") (pin "14") (pinfunction "14_14") (pintype "bidirectional"))
      (node (ref "L_J10") (pin "29") (pinfunction "29_29") (pintype "bidirectional"))
      (node (ref "R56") (pin "2") (pinfunction "2_2") (pintype "passive"))
    )
    (net (code "130") (name "IN_11") (class "Default")
      (node (ref "J9") (pin "15") (pinfunction "15_15") (pintype "bidirectional"))
      (node (ref "L_J10") (pin "30") (pinfunction "30_30") (pintype "bidirectional"))
      (node (ref "R55") (pin "2") (pinfunction "2_2") (pintype "passive"))
    )
    (net (code "131") (name "IN_12") (class "Default")
      (node (ref "J9") (pin "16") (pinfunction "16_16") (pintype "bidirectional"))
      (node (ref "L_J10") (pin "31") (pinfunction "31_31") (pintype "bidirectional"))
      (node (ref "R54") (pin "2") (pinfunction "2_2") (pintype "passive"))
    )
    (net (code "132") (name "IN_13") (class "Default")
      (node (ref "J9") (pin "17") (pinfunction "17_17") (pintype "bidirectional"))
      (node (ref "L_J10") (pin "32") (pinfunction "32_32") (pintype "bidirectional"))
      (node (ref "R53") (pin "2") (pinfunction "2_2") (pintype "passive"))
    )
    (net (code "133") (name "IN_14") (class "Default")
      (node (ref "J9") (pin "18") (pinfunction "18_18") (pintype "bidirectional"))
      (node (ref "L_J10") (pin "33") (pinfunction "33_33") (pintype "bidirectional"))
      (node (ref "R52") (pin "2") (pinfunction "2_2") (pintype "passive"))
    )
    (net (code "134") (name "IN_15") (class "Default")
      (node (ref "J9") (pin "19") (pinfunction "19_19") (pintype "bidirectional"))
      (node (ref "L_J10") (pin "34") (pinfunction "34_34") (pintype "bidirectional"))
      (node (ref "R51") (pin "2") (pinfunction "2_2") (pintype "passive"))
    )
    (net (code "135") (name "Net-(IC1A-DIR)") (class "Default")
      (node (ref "IC1") (pin "1") (pinfunction "DIR_1") (pintype "input"))
      (node (ref "R41") (pin "1") (pinfunction "1_1") (pintype "passive"))
    )
    (net (code "136") (name "Net-(IC2A-DIR)") (class "Default")
      (node (ref "IC2") (pin "1") (pinfunction "DIR_1") (pintype "input"))
      (node (ref "IC3") (pin "1") (pinfunction "DIR_1") (pintype "input"))
      (node (ref "IC4") (pin "1") (pinfunction "DIR_1") (pintype "input"))
      (node (ref "IC5") (pin "1") (pinfunction "DIR_1") (pintype "input"))
      (node (ref "R40") (pin "1") (pinfunction "1_1") (pintype "passive"))
    )
    (net (code "137") (name "Net-(IC7A-DIR)") (class "Default")
      (node (ref "IC7") (pin "1") (pinfunction "DIR_1") (pintype "input"))
      (node (ref "R5") (pin "1") (pinfunction "1_1") (pintype "passive"))
    )
    (net (code "138") (name "Net-(IC8-RA0{slash}ICSPDAT)") (class "Default")
      (node (ref "IC8") (pin "19") (pinfunction "RA0/ICSPDAT_19") (pintype "bidirectional"))
      (node (ref "J22") (pin "4") (pinfunction "4_4") (pintype "passive"))
    )
    (net (code "139") (name "Net-(IC8-RA1{slash}ICSPCLK)") (class "Default")
      (node (ref "IC8") (pin "18") (pinfunction "RA1/ICSPCLK_18") (pintype "bidirectional"))
      (node (ref "J22") (pin "5") (pinfunction "5_5") (pintype "passive"))
    )
    (net (code "140") (name "Net-(IC8-~{MCLR}{slash}VPP{slash}RA3)") (class "Default")
      (node (ref "IC8") (pin "4") (pinfunction "~{MCLR}/VPP/RA3_4") (pintype "bidirectional"))
      (node (ref "J22") (pin "1") (pinfunction "1_1") (pintype "passive"))
    )
    (net (code "141") (name "Net-(OSC1-FQ)") (class "Default")
      (node (ref "OSC1") (pin "5") (pinfunction "FQ_5") (pintype "output"))
      (node (ref "R1") (pin "2") (pinfunction "2_2") (pintype "passive"))
    )
    (net (code "142") (name "OUT_0") (class "Default")
      (node (ref "J11") (pin "2") (pinfunction "2_2") (pintype "bidirectional"))
      (node (ref "L_J10") (pin "3") (pinfunction "3_3") (pintype "bidirectional"))
      (node (ref "TP4") (pin "P$1") (pinfunction "P$1_P$1") (pintype "bidirectional"))
    )
    (net (code "143") (name "OUT_1") (class "Default")
      (node (ref "J11") (pin "3") (pinfunction "3_3") (pintype "bidirectional"))
      (node (ref "L_J10") (pin "4") (pinfunction "4_4") (pintype "bidirectional"))
      (node (ref "TP5") (pin "P$1") (pinfunction "P$1_P$1") (pintype "bidirectional"))
    )
    (net (code "144") (name "OUT_2") (class "Default")
      (node (ref "J11") (pin "4") (pinfunction "4_4") (pintype "bidirectional"))
      (node (ref "L_J10") (pin "5") (pinfunction "5_5") (pintype "bidirectional"))
      (node (ref "TP6") (pin "P$1") (pinfunction "P$1_P$1") (pintype "bidirectional"))
    )
    (net (code "145") (name "OUT_3") (class "Default")
      (node (ref "J11") (pin "5") (pinfunction "5_5") (pintype "bidirectional"))
      (node (ref "L_J10") (pin "6") (pinfunction "6_6") (pintype "bidirectional"))
      (node (ref "TP9") (pin "P$1") (pinfunction "P$1_P$1") (pintype "bidirectional"))
    )
    (net (code "146") (name "OUT_4") (class "Default")
      (node (ref "J11") (pin "6") (pinfunction "6_6") (pintype "bidirectional"))
      (node (ref "L_J10") (pin "7") (pinfunction "7_7") (pintype "bidirectional"))
    )
    (net (code "147") (name "OUT_5") (class "Default")
      (node (ref "J11") (pin "7") (pinfunction "7_7") (pintype "bidirectional"))
      (node (ref "L_J10") (pin "8") (pinfunction "8_8") (pintype "bidirectional"))
    )
    (net (code "148") (name "OUT_6") (class "Default")
      (node (ref "J11") (pin "8") (pinfunction "8_8") (pintype "bidirectional"))
      (node (ref "L_J10") (pin "9") (pinfunction "9_9") (pintype "bidirectional"))
    )
    (net (code "149") (name "OUT_7") (class "Default")
      (node (ref "J11") (pin "9") (pinfunction "9_9") (pintype "bidirectional"))
      (node (ref "L_J10") (pin "10") (pinfunction "10_10") (pintype "bidirectional"))
    )
    (net (code "150") (name "OUT_8") (class "Default")
      (node (ref "J11") (pin "12") (pinfunction "12_12") (pintype "bidirectional"))
      (node (ref "L_J10") (pin "11") (pinfunction "11_11") (pintype "bidirectional"))
    )
    (net (code "151") (name "OUT_9") (class "Default")
      (node (ref "J11") (pin "13") (pinfunction "13_13") (pintype "bidirectional"))
      (node (ref "L_J10") (pin "12") (pinfunction "12_12") (pintype "bidirectional"))
    )
    (net (code "152") (name "OUT_10") (class "Default")
      (node (ref "J11") (pin "14") (pinfunction "14_14") (pintype "bidirectional"))
      (node (ref "L_J10") (pin "13") (pinfunction "13_13") (pintype "bidirectional"))
    )
    (net (code "153") (name "OUT_11") (class "Default")
      (node (ref "J11") (pin "15") (pinfunction "15_15") (pintype "bidirectional"))
      (node (ref "L_J10") (pin "14") (pinfunction "14_14") (pintype "bidirectional"))
    )
    (net (code "154") (name "OUT_12") (class "Default")
      (node (ref "J11") (pin "16") (pinfunction "16_16") (pintype "bidirectional"))
      (node (ref "L_J10") (pin "15") (pinfunction "15_15") (pintype "bidirectional"))
    )
    (net (code "155") (name "OUT_13") (class "Default")
      (node (ref "J11") (pin "17") (pinfunction "17_17") (pintype "bidirectional"))
      (node (ref "L_J10") (pin "16") (pinfunction "16_16") (pintype "bidirectional"))
    )
    (net (code "156") (name "OUT_14") (class "Default")
      (node (ref "J11") (pin "18") (pinfunction "18_18") (pintype "bidirectional"))
      (node (ref "L_J10") (pin "17") (pinfunction "17_17") (pintype "bidirectional"))
    )
    (net (code "157") (name "OUT_15") (class "Default")
      (node (ref "J11") (pin "19") (pinfunction "19_19") (pintype "bidirectional"))
      (node (ref "L_J10") (pin "18") (pinfunction "18_18") (pintype "bidirectional"))
    )
    (net (code "158") (name "RD0") (class "Default")
      (node (ref "IC1") (pin "18") (pinfunction "B1_18") (pintype "bidirectional"))
      (node (ref "J7") (pin "2") (pinfunction "2_2") (pintype "bidirectional"))
    )
    (net (code "159") (name "RD1") (class "Default")
      (node (ref "IC1") (pin "17") (pinfunction "B2_17") (pintype "bidirectional"))
      (node (ref "J7") (pin "3") (pinfunction "3_3") (pintype "bidirectional"))
    )
    (net (code "160") (name "RD2") (class "Default")
      (node (ref "IC1") (pin "16") (pinfunction "B3_16") (pintype "bidirectional"))
      (node (ref "J7") (pin "4") (pinfunction "4_4") (pintype "bidirectional"))
    )
    (net (code "161") (name "RD3") (class "Default")
      (node (ref "IC1") (pin "15") (pinfunction "B4_15") (pintype "bidirectional"))
      (node (ref "J7") (pin "5") (pinfunction "5_5") (pintype "bidirectional"))
    )
    (net (code "162") (name "RD4") (class "Default")
      (node (ref "IC1") (pin "14") (pinfunction "B5_14") (pintype "bidirectional"))
      (node (ref "J7") (pin "6") (pinfunction "6_6") (pintype "bidirectional"))
    )
    (net (code "163") (name "RD5") (class "Default")
      (node (ref "IC1") (pin "13") (pinfunction "B6_13") (pintype "bidirectional"))
      (node (ref "J7") (pin "7") (pinfunction "7_7") (pintype "bidirectional"))
    )
    (net (code "164") (name "RD6") (class "Default")
      (node (ref "IC1") (pin "12") (pinfunction "B7_12") (pintype "bidirectional"))
      (node (ref "J7") (pin "8") (pinfunction "8_8") (pintype "bidirectional"))
    )
    (net (code "165") (name "RD7") (class "Default")
      (node (ref "IC1") (pin "11") (pinfunction "B8_11") (pintype "bidirectional"))
      (node (ref "J7") (pin "9") (pinfunction "9_9") (pintype "bidirectional"))
    )
    (net (code "166") (name "RESET_N") (class "Default")
      (node (ref "IC8") (pin "6") (pinfunction "RC4_6") (pintype "bidirectional"))
      (node (ref "L_J7") (pin "23") (pinfunction "23_23") (pintype "bidirectional"))
    )
    (net (code "167") (name "SPEED") (class "Default")
      (node (ref "IC8") (pin "16") (pinfunction "RC0_16") (pintype "bidirectional"))
      (node (ref "TP10") (pin "P$1") (pinfunction "P$1_P$1") (pintype "bidirectional"))
    )
    (net (code "168") (name "SPI_CLK") (class "Default")
      (node (ref "IC8") (pin "11") (pinfunction "RB6_11") (pintype "bidirectional"))
      (node (ref "L_J7") (pin "26") (pinfunction "26_26") (pintype "bidirectional"))
    )
    (net (code "169") (name "SPI_MISO") (class "Default")
      (node (ref "IC8") (pin "13") (pinfunction "RB4_13") (pintype "bidirectional"))
      (node (ref "L_J7") (pin "29") (pinfunction "29_29") (pintype "bidirectional"))
    )
    (net (code "170") (name "SPI_MOSI") (class "Default")
      (node (ref "IC8") (pin "9") (pinfunction "RC7_9") (pintype "bidirectional"))
      (node (ref "L_J7") (pin "28") (pinfunction "28_28") (pintype "bidirectional"))
    )
    (net (code "171") (name "UART_RX") (class "Default")
      (node (ref "IC8") (pin "12") (pinfunction "RB5_12") (pintype "bidirectional"))
      (node (ref "J6") (pin "3") (pinfunction "3_3") (pintype "passive"))
    )
    (net (code "172") (name "UART_TX") (class "Default")
      (node (ref "IC8") (pin "10") (pinfunction "RB7_10") (pintype "bidirectional"))
      (node (ref "J6") (pin "1") (pinfunction "1_1") (pintype "passive"))
    )
    (net (code "173") (name "USER_INT") (class "Default")
      (node (ref "L_J4") (pin "9") (pinfunction "9_9") (pintype "bidirectional"))
      (node (ref "R39") (pin "1") (pinfunction "1_1") (pintype "passive"))
      (node (ref "TP2") (pin "P$1") (pinfunction "P$1_P$1") (pintype "bidirectional"))
    )
    (net (code "174") (name "USER_RESET") (class "Default")
      (node (ref "IC7") (pin "6") (pinfunction "A5_6") (pintype "bidirectional"))
      (node (ref "L_J10") (pin "36") (pinfunction "36_36") (pintype "bidirectional"))
    )
    (net (code "175") (name "USER_RESET_3V3") (class "Default")
      (node (ref "IC7") (pin "14") (pinfunction "B5_14") (pintype "bidirectional"))
      (node (ref "J2") (pin "4") (pinfunction "4_4") (pintype "passive"))
    )
    (net (code "176") (name "WD0") (class "Default")
      (node (ref "IC5") (pin "18") (pinfunction "B1_18") (pintype "bidirectional"))
      (node (ref "J7") (pin "12") (pinfunction "12_12") (pintype "bidirectional"))
    )
    (net (code "177") (name "WD1") (class "Default")
      (node (ref "IC5") (pin "17") (pinfunction "B2_17") (pintype "bidirectional"))
      (node (ref "J7") (pin "13") (pinfunction "13_13") (pintype "bidirectional"))
    )
    (net (code "178") (name "WD2") (class "Default")
      (node (ref "IC5") (pin "16") (pinfunction "B3_16") (pintype "bidirectional"))
      (node (ref "J7") (pin "14") (pinfunction "14_14") (pintype "bidirectional"))
    )
    (net (code "179") (name "WD3") (class "Default")
      (node (ref "IC5") (pin "15") (pinfunction "B4_15") (pintype "bidirectional"))
      (node (ref "J7") (pin "15") (pinfunction "15_15") (pintype "bidirectional"))
    )
    (net (code "180") (name "WD4") (class "Default")
      (node (ref "IC5") (pin "14") (pinfunction "B5_14") (pintype "bidirectional"))
      (node (ref "J7") (pin "16") (pinfunction "16_16") (pintype "bidirectional"))
    )
    (net (code "181") (name "WD5") (class "Default")
      (node (ref "IC5") (pin "13") (pinfunction "B6_13") (pintype "bidirectional"))
      (node (ref "J7") (pin "17") (pinfunction "17_17") (pintype "bidirectional"))
    )
    (net (code "182") (name "WD6") (class "Default")
      (node (ref "IC5") (pin "12") (pinfunction "B7_12") (pintype "bidirectional"))
      (node (ref "J7") (pin "18") (pinfunction "18_18") (pintype "bidirectional"))
    )
    (net (code "183") (name "WD7") (class "Default")
      (node (ref "IC5") (pin "11") (pinfunction "B8_11") (pintype "bidirectional"))
      (node (ref "J7") (pin "19") (pinfunction "19_19") (pintype "bidirectional"))
    )
    (net (code "184") (name "WRITE_N") (class "Default")
      (node (ref "IC3") (pin "3") (pinfunction "A2_3") (pintype "bidirectional"))
      (node (ref "J1") (pin "3") (pinfunction "3_3") (pintype "bidirectional"))
    )
    (net (code "185") (name "unconnected-(IC3A-B4-Pad15)") (class "Default")
      (node (ref "IC3") (pin "15") (pinfunction "B4_15") (pintype "bidirectional"))
    )
    (net (code "186") (name "unconnected-(IC3A-B5-Pad14)") (class "Default")
      (node (ref "IC3") (pin "14") (pinfunction "B5_14") (pintype "bidirectional"))
    )
    (net (code "187") (name "unconnected-(IC3A-B6-Pad13)") (class "Default")
      (node (ref "IC3") (pin "13") (pinfunction "B6_13") (pintype "bidirectional"))
    )
    (net (code "188") (name "unconnected-(IC3A-B7-Pad12)") (class "Default")
      (node (ref "IC3") (pin "12") (pinfunction "B7_12") (pintype "bidirectional"))
    )
    (net (code "189") (name "unconnected-(IC3A-B8-Pad11)") (class "Default")
      (node (ref "IC3") (pin "11") (pinfunction "B8_11") (pintype "bidirectional"))
    )
    (net (code "190") (name "unconnected-(IC8-RA2-Pad17)") (class "Default")
      (node (ref "IC8") (pin "17") (pinfunction "RA2_17") (pintype "bidirectional"))
    )
    (net (code "191") (name "unconnected-(IC8-RA4-Pad3)") (class "Default")
      (node (ref "IC8") (pin "3") (pinfunction "RA4_3") (pintype "bidirectional"))
    )
    (net (code "192") (name "unconnected-(IC8-RA5-Pad2)") (class "Default")
      (node (ref "IC8") (pin "2") (pinfunction "RA5_2") (pintype "bidirectional"))
    )
    (net (code "193") (name "unconnected-(IC8-RC1-Pad15)") (class "Default")
      (node (ref "IC8") (pin "15") (pinfunction "RC1_15") (pintype "bidirectional"))
    )
    (net (code "194") (name "unconnected-(IC8-RC2-Pad14)") (class "Default")
      (node (ref "IC8") (pin "14") (pinfunction "RC2_14") (pintype "bidirectional"))
    )
    (net (code "195") (name "unconnected-(IC8-RC3-Pad7)") (class "Default")
      (node (ref "IC8") (pin "7") (pinfunction "RC3_7") (pintype "bidirectional"))
    )
    (net (code "196") (name "unconnected-(J14-D+-Pad3)") (class "Default")
      (node (ref "J14") (pin "3") (pinfunction "D+_3") (pintype "bidirectional"))
    )
    (net (code "197") (name "unconnected-(J14-D--Pad2)") (class "Default")
      (node (ref "J14") (pin "2") (pinfunction "D-_2") (pintype "bidirectional"))
    )
    (net (code "198") (name "unconnected-(J22-Pad6)") (class "Default")
      (node (ref "J22") (pin "6") (pinfunction "6_6") (pintype "passive"))
    )
    (net (code "199") (name "unconnected-(L_J3-Pad1)") (class "Default")
      (node (ref "L_J3") (pin "1") (pinfunction "1_1") (pintype "bidirectional"))
    )
    (net (code "200") (name "unconnected-(L_J3-Pad2)") (class "Default")
      (node (ref "L_J3") (pin "2") (pinfunction "2_2") (pintype "bidirectional"))
    )
    (net (code "201") (name "unconnected-(L_J3-Pad3)") (class "Default")
      (node (ref "L_J3") (pin "3") (pinfunction "3_3") (pintype "bidirectional"))
    )
    (net (code "202") (name "unconnected-(L_J3-Pad4)") (class "Default")
      (node (ref "L_J3") (pin "4") (pinfunction "4_4") (pintype "bidirectional"))
    )
    (net (code "203") (name "unconnected-(L_J3-Pad5)") (class "Default")
      (node (ref "L_J3") (pin "5") (pinfunction "5_5") (pintype "bidirectional"))
    )
    (net (code "204") (name "unconnected-(L_J3-Pad6)") (class "Default")
      (node (ref "L_J3") (pin "6") (pinfunction "6_6") (pintype "bidirectional"))
    )
    (net (code "205") (name "unconnected-(L_J3-Pad7)") (class "Default")
      (node (ref "L_J3") (pin "7") (pinfunction "7_7") (pintype "bidirectional"))
    )
    (net (code "206") (name "unconnected-(L_J3-Pad8)") (class "Default")
      (node (ref "L_J3") (pin "8") (pinfunction "8_8") (pintype "bidirectional"))
    )
    (net (code "207") (name "unconnected-(L_J3-Pad9)") (class "Default")
      (node (ref "L_J3") (pin "9") (pinfunction "9_9") (pintype "bidirectional"))
    )
    (net (code "208") (name "unconnected-(L_J3-Pad10)") (class "Default")
      (node (ref "L_J3") (pin "10") (pinfunction "10_10") (pintype "bidirectional"))
    )
    (net (code "209") (name "unconnected-(L_J3-Pad11)") (class "Default")
      (node (ref "L_J3") (pin "11") (pinfunction "11_11") (pintype "bidirectional"))
    )
    (net (code "210") (name "unconnected-(L_J3-Pad12)") (class "Default")
      (node (ref "L_J3") (pin "12") (pinfunction "12_12") (pintype "bidirectional"))
    )
    (net (code "211") (name "unconnected-(L_J3-Pad13)") (class "Default")
      (node (ref "L_J3") (pin "13") (pinfunction "13_13") (pintype "bidirectional"))
    )
    (net (code "212") (name "unconnected-(L_J3-Pad14)") (class "Default")
      (node (ref "L_J3") (pin "14") (pinfunction "14_14") (pintype "bidirectional"))
    )
    (net (code "213") (name "unconnected-(L_J3-Pad15)") (class "Default")
      (node (ref "L_J3") (pin "15") (pinfunction "15_15") (pintype "bidirectional"))
    )
    (net (code "214") (name "unconnected-(L_J3-Pad16)") (class "Default")
      (node (ref "L_J3") (pin "16") (pinfunction "16_16") (pintype "bidirectional"))
    )
    (net (code "215") (name "unconnected-(L_J3-Pad17)") (class "Default")
      (node (ref "L_J3") (pin "17") (pinfunction "17_17") (pintype "bidirectional"))
    )
    (net (code "216") (name "unconnected-(L_J3-Pad18)") (class "Default")
      (node (ref "L_J3") (pin "18") (pinfunction "18_18") (pintype "bidirectional"))
    )
    (net (code "217") (name "unconnected-(L_J3-Pad19)") (class "Default")
      (node (ref "L_J3") (pin "19") (pinfunction "19_19") (pintype "bidirectional"))
    )
    (net (code "218") (name "unconnected-(L_J3-Pad20)") (class "Default")
      (node (ref "L_J3") (pin "20") (pinfunction "20_20") (pintype "bidirectional"))
    )
    (net (code "219") (name "unconnected-(L_J3-Pad21)") (class "Default")
      (node (ref "L_J3") (pin "21") (pinfunction "21_21") (pintype "bidirectional"))
    )
    (net (code "220") (name "unconnected-(L_J3-Pad22)") (class "Default")
      (node (ref "L_J3") (pin "22") (pinfunction "22_22") (pintype "bidirectional"))
    )
    (net (code "221") (name "unconnected-(L_J3-Pad23)") (class "Default")
      (node (ref "L_J3") (pin "23") (pinfunction "23_23") (pintype "bidirectional"))
    )
    (net (code "222") (name "unconnected-(L_J3-Pad24)") (class "Default")
      (node (ref "L_J3") (pin "24") (pinfunction "24_24") (pintype "bidirectional"))
    )
    (net (code "223") (name "unconnected-(L_J3-Pad25)") (class "Default")
      (node (ref "L_J3") (pin "25") (pinfunction "25_25") (pintype "bidirectional"))
    )
    (net (code "224") (name "unconnected-(L_J3-Pad26)") (class "Default")
      (node (ref "L_J3") (pin "26") (pinfunction "26_26") (pintype "bidirectional"))
    )
    (net (code "225") (name "unconnected-(L_J3-Pad27)") (class "Default")
      (node (ref "L_J3") (pin "27") (pinfunction "27_27") (pintype "bidirectional"))
    )
    (net (code "226") (name "unconnected-(L_J3-Pad28)") (class "Default")
      (node (ref "L_J3") (pin "28") (pinfunction "28_28") (pintype "bidirectional"))
    )
    (net (code "227") (name "unconnected-(L_J3-Pad29)") (class "Default")
      (node (ref "L_J3") (pin "29") (pinfunction "29_29") (pintype "bidirectional"))
    )
    (net (code "228") (name "unconnected-(L_J3-Pad30)") (class "Default")
      (node (ref "L_J3") (pin "30") (pinfunction "30_30") (pintype "bidirectional"))
    )
    (net (code "229") (name "unconnected-(L_J3-Pad31)") (class "Default")
      (node (ref "L_J3") (pin "31") (pinfunction "31_31") (pintype "bidirectional"))
    )
    (net (code "230") (name "unconnected-(L_J3-Pad32)") (class "Default")
      (node (ref "L_J3") (pin "32") (pinfunction "32_32") (pintype "bidirectional"))
    )
    (net (code "231") (name "unconnected-(L_J3-Pad33)") (class "Default")
      (node (ref "L_J3") (pin "33") (pinfunction "33_33") (pintype "bidirectional"))
    )
    (net (code "232") (name "unconnected-(L_J3-Pad34)") (class "Default")
      (node (ref "L_J3") (pin "34") (pinfunction "34_34") (pintype "bidirectional"))
    )
    (net (code "233") (name "unconnected-(L_J3-Pad35)") (class "Default")
      (node (ref "L_J3") (pin "35") (pinfunction "35_35") (pintype "bidirectional"))
    )
    (net (code "234") (name "unconnected-(L_J3-Pad36)") (class "Default")
      (node (ref "L_J3") (pin "36") (pinfunction "36_36") (pintype "bidirectional"))
    )
    (net (code "235") (name "unconnected-(L_J3-Pad37)") (class "Default")
      (node (ref "L_J3") (pin "37") (pinfunction "37_37") (pintype "bidirectional"))
    )
    (net (code "236") (name "unconnected-(L_J3-Pad38)") (class "Default")
      (node (ref "L_J3") (pin "38") (pinfunction "38_38") (pintype "bidirectional"))
    )
    (net (code "237") (name "unconnected-(L_J3-Pad39)") (class "Default")
      (node (ref "L_J3") (pin "39") (pinfunction "39_39") (pintype "bidirectional"))
    )
    (net (code "238") (name "unconnected-(L_J3-Pad40)") (class "Default")
      (node (ref "L_J3") (pin "40") (pinfunction "40_40") (pintype "bidirectional"))
    )
    (net (code "239") (name "unconnected-(L_J4-Pad1)") (class "Default")
      (node (ref "L_J4") (pin "1") (pinfunction "1_1") (pintype "bidirectional"))
    )
    (net (code "240") (name "unconnected-(L_J4-Pad3)") (class "Default")
      (node (ref "L_J4") (pin "3") (pinfunction "3_3") (pintype "bidirectional"))
    )
    (net (code "241") (name "unconnected-(L_J4-Pad5)") (class "Default")
      (node (ref "L_J4") (pin "5") (pinfunction "5_5") (pintype "bidirectional"))
    )
    (net (code "242") (name "unconnected-(L_J4-Pad7)") (class "Default")
      (node (ref "L_J4") (pin "7") (pinfunction "7_7") (pintype "bidirectional"))
    )
    (net (code "243") (name "unconnected-(L_J4-Pad25)") (class "Default")
      (node (ref "L_J4") (pin "25") (pinfunction "25_25") (pintype "bidirectional"))
    )
    (net (code "244") (name "unconnected-(L_J4-Pad27)") (class "Default")
      (node (ref "L_J4") (pin "27") (pinfunction "27_27") (pintype "bidirectional"))
    )
    (net (code "245") (name "unconnected-(L_J4-Pad28)") (class "Default")
      (node (ref "L_J4") (pin "28") (pinfunction "28_28") (pintype "bidirectional"))
    )
    (net (code "246") (name "unconnected-(L_J4-Pad37)") (class "Default")
      (node (ref "L_J4") (pin "37") (pinfunction "37_37") (pintype "bidirectional"))
    )
    (net (code "247") (name "unconnected-(L_J4-Pad38)") (class "Default")
      (node (ref "L_J4") (pin "38") (pinfunction "38_38") (pintype "bidirectional"))
    )
    (net (code "248") (name "unconnected-(L_J4-Pad39)") (class "Default")
      (node (ref "L_J4") (pin "39") (pinfunction "39_39") (pintype "bidirectional"))
    )
    (net (code "249") (name "unconnected-(L_J4-Pad40)") (class "Default")
      (node (ref "L_J4") (pin "40") (pinfunction "40_40") (pintype "bidirectional"))
    )
    (net (code "250") (name "unconnected-(L_J5-Pad1)") (class "Default")
      (node (ref "L_J5") (pin "1") (pinfunction "1_1") (pintype "bidirectional"))
    )
    (net (code "251") (name "unconnected-(L_J5-Pad2)") (class "Default")
      (node (ref "L_J5") (pin "2") (pinfunction "2_2") (pintype "bidirectional"))
    )
    (net (code "252") (name "unconnected-(L_J5-Pad32)") (class "Default")
      (node (ref "L_J5") (pin "32") (pinfunction "32_32") (pintype "bidirectional"))
    )
    (net (code "253") (name "unconnected-(L_J5-Pad33)") (class "Default")
      (node (ref "L_J5") (pin "33") (pinfunction "33_33") (pintype "bidirectional"))
    )
    (net (code "254") (name "unconnected-(L_J5-Pad34)") (class "Default")
      (node (ref "L_J5") (pin "34") (pinfunction "34_34") (pintype "bidirectional"))
    )
    (net (code "255") (name "unconnected-(L_J5-Pad35)") (class "Default")
      (node (ref "L_J5") (pin "35") (pinfunction "35_35") (pintype "bidirectional"))
    )
    (net (code "256") (name "unconnected-(L_J5-Pad36)") (class "Default")
      (node (ref "L_J5") (pin "36") (pinfunction "36_36") (pintype "bidirectional"))
    )
    (net (code "257") (name "unconnected-(L_J6-Pad1)") (class "Default")
      (node (ref "L_J6") (pin "1") (pinfunction "1_1") (pintype "bidirectional"))
    )
    (net (code "258") (name "unconnected-(L_J6-Pad2)") (class "Default")
      (node (ref "L_J6") (pin "2") (pinfunction "2_2") (pintype "bidirectional"))
    )
    (net (code "259") (name "unconnected-(L_J6-Pad3)") (class "Default")
      (node (ref "L_J6") (pin "3") (pinfunction "3_3") (pintype "bidirectional"))
    )
    (net (code "260") (name "unconnected-(L_J6-Pad4)") (class "Default")
      (node (ref "L_J6") (pin "4") (pinfunction "4_4") (pintype "bidirectional"))
    )
    (net (code "261") (name "unconnected-(L_J6-Pad5)") (class "Default")
      (node (ref "L_J6") (pin "5") (pinfunction "5_5") (pintype "bidirectional"))
    )
    (net (code "262") (name "unconnected-(L_J6-Pad6)") (class "Default")
      (node (ref "L_J6") (pin "6") (pinfunction "6_6") (pintype "bidirectional"))
    )
    (net (code "263") (name "unconnected-(L_J6-Pad7)") (class "Default")
      (node (ref "L_J6") (pin "7") (pinfunction "7_7") (pintype "bidirectional"))
    )
    (net (code "264") (name "unconnected-(L_J6-Pad8)") (class "Default")
      (node (ref "L_J6") (pin "8") (pinfunction "8_8") (pintype "bidirectional"))
    )
    (net (code "265") (name "unconnected-(L_J6-Pad9)") (class "Default")
      (node (ref "L_J6") (pin "9") (pinfunction "9_9") (pintype "bidirectional"))
    )
    (net (code "266") (name "unconnected-(L_J6-Pad10)") (class "Default")
      (node (ref "L_J6") (pin "10") (pinfunction "10_10") (pintype "bidirectional"))
    )
    (net (code "267") (name "unconnected-(L_J6-Pad11)") (class "Default")
      (node (ref "L_J6") (pin "11") (pinfunction "11_11") (pintype "bidirectional"))
    )
    (net (code "268") (name "unconnected-(L_J6-Pad12)") (class "Default")
      (node (ref "L_J6") (pin "12") (pinfunction "12_12") (pintype "bidirectional"))
    )
    (net (code "269") (name "unconnected-(L_J6-Pad13)") (class "Default")
      (node (ref "L_J6") (pin "13") (pinfunction "13_13") (pintype "bidirectional"))
    )
    (net (code "270") (name "unconnected-(L_J6-Pad14)") (class "Default")
      (node (ref "L_J6") (pin "14") (pinfunction "14_14") (pintype "bidirectional"))
    )
    (net (code "271") (name "unconnected-(L_J6-Pad15)") (class "Default")
      (node (ref "L_J6") (pin "15") (pinfunction "15_15") (pintype "bidirectional"))
    )
    (net (code "272") (name "unconnected-(L_J6-Pad16)") (class "Default")
      (node (ref "L_J6") (pin "16") (pinfunction "16_16") (pintype "bidirectional"))
    )
    (net (code "273") (name "unconnected-(L_J6-Pad17)") (class "Default")
      (node (ref "L_J6") (pin "17") (pinfunction "17_17") (pintype "bidirectional"))
    )
    (net (code "274") (name "unconnected-(L_J6-Pad18)") (class "Default")
      (node (ref "L_J6") (pin "18") (pinfunction "18_18") (pintype "bidirectional"))
    )
    (net (code "275") (name "unconnected-(L_J6-Pad19)") (class "Default")
      (node (ref "L_J6") (pin "19") (pinfunction "19_19") (pintype "bidirectional"))
    )
    (net (code "276") (name "unconnected-(L_J6-Pad20)") (class "Default")
      (node (ref "L_J6") (pin "20") (pinfunction "20_20") (pintype "bidirectional"))
    )
    (net (code "277") (name "unconnected-(L_J6-Pad21)") (class "Default")
      (node (ref "L_J6") (pin "21") (pinfunction "21_21") (pintype "bidirectional"))
    )
    (net (code "278") (name "unconnected-(L_J6-Pad22)") (class "Default")
      (node (ref "L_J6") (pin "22") (pinfunction "22_22") (pintype "bidirectional"))
    )
    (net (code "279") (name "unconnected-(L_J6-Pad23)") (class "Default")
      (node (ref "L_J6") (pin "23") (pinfunction "23_23") (pintype "bidirectional"))
    )
    (net (code "280") (name "unconnected-(L_J6-Pad24)") (class "Default")
      (node (ref "L_J6") (pin "24") (pinfunction "24_24") (pintype "bidirectional"))
    )
    (net (code "281") (name "unconnected-(L_J6-Pad25)") (class "Default")
      (node (ref "L_J6") (pin "25") (pinfunction "25_25") (pintype "bidirectional"))
    )
    (net (code "282") (name "unconnected-(L_J6-Pad26)") (class "Default")
      (node (ref "L_J6") (pin "26") (pinfunction "26_26") (pintype "bidirectional"))
    )
    (net (code "283") (name "unconnected-(L_J6-Pad27)") (class "Default")
      (node (ref "L_J6") (pin "27") (pinfunction "27_27") (pintype "bidirectional"))
    )
    (net (code "284") (name "unconnected-(L_J6-Pad28)") (class "Default")
      (node (ref "L_J6") (pin "28") (pinfunction "28_28") (pintype "bidirectional"))
    )
    (net (code "285") (name "unconnected-(L_J6-Pad29)") (class "Default")
      (node (ref "L_J6") (pin "29") (pinfunction "29_29") (pintype "bidirectional"))
    )
    (net (code "286") (name "unconnected-(L_J6-Pad30)") (class "Default")
      (node (ref "L_J6") (pin "30") (pinfunction "30_30") (pintype "bidirectional"))
    )
    (net (code "287") (name "unconnected-(L_J6-Pad31)") (class "Default")
      (node (ref "L_J6") (pin "31") (pinfunction "31_31") (pintype "bidirectional"))
    )
    (net (code "288") (name "unconnected-(L_J6-Pad32)") (class "Default")
      (node (ref "L_J6") (pin "32") (pinfunction "32_32") (pintype "bidirectional"))
    )
    (net (code "289") (name "unconnected-(L_J6-Pad33)") (class "Default")
      (node (ref "L_J6") (pin "33") (pinfunction "33_33") (pintype "bidirectional"))
    )
    (net (code "290") (name "unconnected-(L_J6-Pad34)") (class "Default")
      (node (ref "L_J6") (pin "34") (pinfunction "34_34") (pintype "bidirectional"))
    )
    (net (code "291") (name "unconnected-(L_J6-Pad35)") (class "Default")
      (node (ref "L_J6") (pin "35") (pinfunction "35_35") (pintype "bidirectional"))
    )
    (net (code "292") (name "unconnected-(L_J6-Pad36)") (class "Default")
      (node (ref "L_J6") (pin "36") (pinfunction "36_36") (pintype "bidirectional"))
    )
    (net (code "293") (name "unconnected-(L_J6-Pad37)") (class "Default")
      (node (ref "L_J6") (pin "37") (pinfunction "37_37") (pintype "bidirectional"))
    )
    (net (code "294") (name "unconnected-(L_J6-Pad38)") (class "Default")
      (node (ref "L_J6") (pin "38") (pinfunction "38_38") (pintype "bidirectional"))
    )
    (net (code "295") (name "unconnected-(L_J6-Pad39)") (class "Default")
      (node (ref "L_J6") (pin "39") (pinfunction "39_39") (pintype "bidirectional"))
    )
    (net (code "296") (name "unconnected-(L_J6-Pad40)") (class "Default")
      (node (ref "L_J6") (pin "40") (pinfunction "40_40") (pintype "bidirectional"))
    )
    (net (code "297") (name "unconnected-(L_J7-Pad25)") (class "Default")
      (node (ref "L_J7") (pin "25") (pinfunction "25_25") (pintype "bidirectional"))
    )
    (net (code "298") (name "unconnected-(L_J7-Pad27)") (class "Default")
      (node (ref "L_J7") (pin "27") (pinfunction "27_27") (pintype "bidirectional"))
    )
    (net (code "299") (name "unconnected-(L_J7-Pad39)") (class "Default")
      (node (ref "L_J7") (pin "39") (pinfunction "39_39") (pintype "bidirectional"))
    )
    (net (code "300") (name "unconnected-(L_J7-Pad40)") (class "Default")
      (node (ref "L_J7") (pin "40") (pinfunction "40_40") (pintype "bidirectional"))
    )
    (net (code "301") (name "unconnected-(L_J8-Pad1)") (class "Default")
      (node (ref "L_J8") (pin "1") (pinfunction "1_1") (pintype "bidirectional"))
    )
    (net (code "302") (name "unconnected-(L_J8-Pad2)") (class "Default")
      (node (ref "L_J8") (pin "2") (pinfunction "2_2") (pintype "bidirectional"))
    )
    (net (code "303") (name "unconnected-(L_J8-Pad3)") (class "Default")
      (node (ref "L_J8") (pin "3") (pinfunction "3_3") (pintype "bidirectional"))
    )
    (net (code "304") (name "unconnected-(L_J8-Pad4)") (class "Default")
      (node (ref "L_J8") (pin "4") (pinfunction "4_4") (pintype "bidirectional"))
    )
    (net (code "305") (name "unconnected-(L_J8-Pad5)") (class "Default")
      (node (ref "L_J8") (pin "5") (pinfunction "5_5") (pintype "bidirectional"))
    )
    (net (code "306") (name "unconnected-(L_J8-Pad6)") (class "Default")
      (node (ref "L_J8") (pin "6") (pinfunction "6_6") (pintype "bidirectional"))
    )
    (net (code "307") (name "unconnected-(L_J8-Pad7)") (class "Default")
      (node (ref "L_J8") (pin "7") (pinfunction "7_7") (pintype "bidirectional"))
    )
    (net (code "308") (name "unconnected-(L_J8-Pad8)") (class "Default")
      (node (ref "L_J8") (pin "8") (pinfunction "8_8") (pintype "bidirectional"))
    )
    (net (code "309") (name "unconnected-(L_J8-Pad9)") (class "Default")
      (node (ref "L_J8") (pin "9") (pinfunction "9_9") (pintype "bidirectional"))
    )
    (net (code "310") (name "unconnected-(L_J8-Pad10)") (class "Default")
      (node (ref "L_J8") (pin "10") (pinfunction "10_10") (pintype "bidirectional"))
    )
    (net (code "311") (name "unconnected-(L_J8-Pad11)") (class "Default")
      (node (ref "L_J8") (pin "11") (pinfunction "11_11") (pintype "bidirectional"))
    )
    (net (code "312") (name "unconnected-(L_J8-Pad12)") (class "Default")
      (node (ref "L_J8") (pin "12") (pinfunction "12_12") (pintype "bidirectional"))
    )
    (net (code "313") (name "unconnected-(L_J8-Pad13)") (class "Default")
      (node (ref "L_J8") (pin "13") (pinfunction "13_13") (pintype "bidirectional"))
    )
    (net (code "314") (name "unconnected-(L_J8-Pad14)") (class "Default")
      (node (ref "L_J8") (pin "14") (pinfunction "14_14") (pintype "bidirectional"))
    )
    (net (code "315") (name "unconnected-(L_J8-Pad15)") (class "Default")
      (node (ref "L_J8") (pin "15") (pinfunction "15_15") (pintype "bidirectional"))
    )
    (net (code "316") (name "unconnected-(L_J8-Pad16)") (class "Default")
      (node (ref "L_J8") (pin "16") (pinfunction "16_16") (pintype "bidirectional"))
    )
    (net (code "317") (name "unconnected-(L_J8-Pad17)") (class "Default")
      (node (ref "L_J8") (pin "17") (pinfunction "17_17") (pintype "bidirectional"))
    )
    (net (code "318") (name "unconnected-(L_J8-Pad18)") (class "Default")
      (node (ref "L_J8") (pin "18") (pinfunction "18_18") (pintype "bidirectional"))
    )
    (net (code "319") (name "unconnected-(L_J8-Pad19)") (class "Default")
      (node (ref "L_J8") (pin "19") (pinfunction "19_19") (pintype "bidirectional"))
    )
    (net (code "320") (name "unconnected-(L_J8-Pad20)") (class "Default")
      (node (ref "L_J8") (pin "20") (pinfunction "20_20") (pintype "bidirectional"))
    )
    (net (code "321") (name "unconnected-(L_J8-Pad21)") (class "Default")
      (node (ref "L_J8") (pin "21") (pinfunction "21_21") (pintype "bidirectional"))
    )
    (net (code "322") (name "unconnected-(L_J8-Pad22)") (class "Default")
      (node (ref "L_J8") (pin "22") (pinfunction "22_22") (pintype "bidirectional"))
    )
    (net (code "323") (name "unconnected-(L_J8-Pad23)") (class "Default")
      (node (ref "L_J8") (pin "23") (pinfunction "23_23") (pintype "bidirectional"))
    )
    (net (code "324") (name "unconnected-(L_J8-Pad24)") (class "Default")
      (node (ref "L_J8") (pin "24") (pinfunction "24_24") (pintype "bidirectional"))
    )
    (net (code "325") (name "unconnected-(L_J8-Pad25)") (class "Default")
      (node (ref "L_J8") (pin "25") (pinfunction "25_25") (pintype "bidirectional"))
    )
    (net (code "326") (name "unconnected-(L_J8-Pad26)") (class "Default")
      (node (ref "L_J8") (pin "26") (pinfunction "26_26") (pintype "bidirectional"))
    )
    (net (code "327") (name "unconnected-(L_J8-Pad27)") (class "Default")
      (node (ref "L_J8") (pin "27") (pinfunction "27_27") (pintype "bidirectional"))
    )
    (net (code "328") (name "unconnected-(L_J8-Pad28)") (class "Default")
      (node (ref "L_J8") (pin "28") (pinfunction "28_28") (pintype "bidirectional"))
    )
    (net (code "329") (name "unconnected-(L_J8-Pad29)") (class "Default")
      (node (ref "L_J8") (pin "29") (pinfunction "29_29") (pintype "bidirectional"))
    )
    (net (code "330") (name "unconnected-(L_J8-Pad30)") (class "Default")
      (node (ref "L_J8") (pin "30") (pinfunction "30_30") (pintype "bidirectional"))
    )
    (net (code "331") (name "unconnected-(L_J8-Pad31)") (class "Default")
      (node (ref "L_J8") (pin "31") (pinfunction "31_31") (pintype "bidirectional"))
    )
    (net (code "332") (name "unconnected-(L_J8-Pad32)") (class "Default")
      (node (ref "L_J8") (pin "32") (pinfunction "32_32") (pintype "bidirectional"))
    )
    (net (code "333") (name "unconnected-(L_J8-Pad33)") (class "Default")
      (node (ref "L_J8") (pin "33") (pinfunction "33_33") (pintype "bidirectional"))
    )
    (net (code "334") (name "unconnected-(L_J8-Pad34)") (class "Default")
      (node (ref "L_J8") (pin "34") (pinfunction "34_34") (pintype "bidirectional"))
    )
    (net (code "335") (name "unconnected-(L_J8-Pad35)") (class "Default")
      (node (ref "L_J8") (pin "35") (pinfunction "35_35") (pintype "bidirectional"))
    )
    (net (code "336") (name "unconnected-(L_J8-Pad36)") (class "Default")
      (node (ref "L_J8") (pin "36") (pinfunction "36_36") (pintype "bidirectional"))
    )
    (net (code "337") (name "unconnected-(L_J8-Pad37)") (class "Default")
      (node (ref "L_J8") (pin "37") (pinfunction "37_37") (pintype "bidirectional"))
    )
    (net (code "338") (name "unconnected-(L_J8-Pad38)") (class "Default")
      (node (ref "L_J8") (pin "38") (pinfunction "38_38") (pintype "bidirectional"))
    )
    (net (code "339") (name "unconnected-(L_J8-Pad39)") (class "Default")
      (node (ref "L_J8") (pin "39") (pinfunction "39_39") (pintype "bidirectional"))
    )
    (net (code "340") (name "unconnected-(L_J8-Pad40)") (class "Default")
      (node (ref "L_J8") (pin "40") (pinfunction "40_40") (pintype "bidirectional"))
    )
    (net (code "341") (name "unconnected-(L_J9-Pad1)") (class "Default")
      (node (ref "L_J9") (pin "1") (pinfunction "1_1") (pintype "bidirectional"))
    )
    (net (code "342") (name "unconnected-(L_J9-Pad2)") (class "Default")
      (node (ref "L_J9") (pin "2") (pinfunction "2_2") (pintype "bidirectional"))
    )
    (net (code "343") (name "unconnected-(L_J9-Pad3)") (class "Default")
      (node (ref "L_J9") (pin "3") (pinfunction "3_3") (pintype "bidirectional"))
    )
    (net (code "344") (name "unconnected-(L_J9-Pad4)") (class "Default")
      (node (ref "L_J9") (pin "4") (pinfunction "4_4") (pintype "bidirectional"))
    )
    (net (code "345") (name "unconnected-(L_J9-Pad5)") (class "Default")
      (node (ref "L_J9") (pin "5") (pinfunction "5_5") (pintype "bidirectional"))
    )
    (net (code "346") (name "unconnected-(L_J9-Pad6)") (class "Default")
      (node (ref "L_J9") (pin "6") (pinfunction "6_6") (pintype "bidirectional"))
    )
    (net (code "347") (name "unconnected-(L_J9-Pad7)") (class "Default")
      (node (ref "L_J9") (pin "7") (pinfunction "7_7") (pintype "bidirectional"))
    )
    (net (code "348") (name "unconnected-(L_J9-Pad8)") (class "Default")
      (node (ref "L_J9") (pin "8") (pinfunction "8_8") (pintype "bidirectional"))
    )
    (net (code "349") (name "unconnected-(L_J9-Pad9)") (class "Default")
      (node (ref "L_J9") (pin "9") (pinfunction "9_9") (pintype "bidirectional"))
    )
    (net (code "350") (name "unconnected-(L_J9-Pad10)") (class "Default")
      (node (ref "L_J9") (pin "10") (pinfunction "10_10") (pintype "bidirectional"))
    )
    (net (code "351") (name "unconnected-(L_J9-Pad12)") (class "Default")
      (node (ref "L_J9") (pin "12") (pinfunction "12_12") (pintype "bidirectional"))
    )
    (net (code "352") (name "unconnected-(L_J9-Pad13)") (class "Default")
      (node (ref "L_J9") (pin "13") (pinfunction "13_13") (pintype "bidirectional"))
    )
    (net (code "353") (name "unconnected-(L_J9-Pad14)") (class "Default")
      (node (ref "L_J9") (pin "14") (pinfunction "14_14") (pintype "bidirectional"))
    )
    (net (code "354") (name "unconnected-(L_J9-Pad15)") (class "Default")
      (node (ref "L_J9") (pin "15") (pinfunction "15_15") (pintype "bidirectional"))
    )
    (net (code "355") (name "unconnected-(L_J9-Pad16)") (class "Default")
      (node (ref "L_J9") (pin "16") (pinfunction "16_16") (pintype "bidirectional"))
    )
    (net (code "356") (name "unconnected-(L_J9-Pad17)") (class "Default")
      (node (ref "L_J9") (pin "17") (pinfunction "17_17") (pintype "bidirectional"))
    )
    (net (code "357") (name "unconnected-(L_J9-Pad18)") (class "Default")
      (node (ref "L_J9") (pin "18") (pinfunction "18_18") (pintype "bidirectional"))
    )
    (net (code "358") (name "unconnected-(L_J9-Pad19)") (class "Default")
      (node (ref "L_J9") (pin "19") (pinfunction "19_19") (pintype "bidirectional"))
    )
    (net (code "359") (name "unconnected-(L_J9-Pad20)") (class "Default")
      (node (ref "L_J9") (pin "20") (pinfunction "20_20") (pintype "bidirectional"))
    )
    (net (code "360") (name "unconnected-(L_J9-Pad21)") (class "Default")
      (node (ref "L_J9") (pin "21") (pinfunction "21_21") (pintype "bidirectional"))
    )
    (net (code "361") (name "unconnected-(L_J9-Pad22)") (class "Default")
      (node (ref "L_J9") (pin "22") (pinfunction "22_22") (pintype "bidirectional"))
    )
    (net (code "362") (name "unconnected-(L_J9-Pad23)") (class "Default")
      (node (ref "L_J9") (pin "23") (pinfunction "23_23") (pintype "bidirectional"))
    )
    (net (code "363") (name "unconnected-(L_J9-Pad24)") (class "Default")
      (node (ref "L_J9") (pin "24") (pinfunction "24_24") (pintype "bidirectional"))
    )
    (net (code "364") (name "unconnected-(L_J9-Pad25)") (class "Default")
      (node (ref "L_J9") (pin "25") (pinfunction "25_25") (pintype "bidirectional"))
    )
    (net (code "365") (name "unconnected-(L_J9-Pad26)") (class "Default")
      (node (ref "L_J9") (pin "26") (pinfunction "26_26") (pintype "bidirectional"))
    )
    (net (code "366") (name "unconnected-(L_J9-Pad27)") (class "Default")
      (node (ref "L_J9") (pin "27") (pinfunction "27_27") (pintype "bidirectional"))
    )
    (net (code "367") (name "unconnected-(L_J9-Pad28)") (class "Default")
      (node (ref "L_J9") (pin "28") (pinfunction "28_28") (pintype "bidirectional"))
    )
    (net (code "368") (name "unconnected-(L_J9-Pad29)") (class "Default")
      (node (ref "L_J9") (pin "29") (pinfunction "29_29") (pintype "bidirectional"))
    )
    (net (code "369") (name "unconnected-(L_J9-Pad30)") (class "Default")
      (node (ref "L_J9") (pin "30") (pinfunction "30_30") (pintype "bidirectional"))
    )
    (net (code "370") (name "unconnected-(L_J9-Pad31)") (class "Default")
      (node (ref "L_J9") (pin "31") (pinfunction "31_31") (pintype "bidirectional"))
    )
    (net (code "371") (name "unconnected-(L_J9-Pad32)") (class "Default")
      (node (ref "L_J9") (pin "32") (pinfunction "32_32") (pintype "bidirectional"))
    )
    (net (code "372") (name "unconnected-(L_J9-Pad33)") (class "Default")
      (node (ref "L_J9") (pin "33") (pinfunction "33_33") (pintype "bidirectional"))
    )
    (net (code "373") (name "unconnected-(L_J9-Pad34)") (class "Default")
      (node (ref "L_J9") (pin "34") (pinfunction "34_34") (pintype "bidirectional"))
    )
    (net (code "374") (name "unconnected-(L_J9-Pad35)") (class "Default")
      (node (ref "L_J9") (pin "35") (pinfunction "35_35") (pintype "bidirectional"))
    )
    (net (code "375") (name "unconnected-(L_J9-Pad36)") (class "Default")
      (node (ref "L_J9") (pin "36") (pinfunction "36_36") (pintype "bidirectional"))
    )
    (net (code "376") (name "unconnected-(L_J9-Pad37)") (class "Default")
      (node (ref "L_J9") (pin "37") (pinfunction "37_37") (pintype "bidirectional"))
    )
    (net (code "377") (name "unconnected-(L_J9-Pad38)") (class "Default")
      (node (ref "L_J9") (pin "38") (pinfunction "38_38") (pintype "bidirectional"))
    )
    (net (code "378") (name "unconnected-(L_J9-Pad39)") (class "Default")
      (node (ref "L_J9") (pin "39") (pinfunction "39_39") (pintype "bidirectional"))
    )
    (net (code "379") (name "unconnected-(L_J9-Pad40)") (class "Default")
      (node (ref "L_J9") (pin "40") (pinfunction "40_40") (pintype "bidirectional"))
    )
    (net (code "380") (name "unconnected-(L_J10-Pad1)") (class "Default")
      (node (ref "L_J10") (pin "1") (pinfunction "1_1") (pintype "bidirectional"))
    )
    (net (code "381") (name "unconnected-(L_J10-Pad2)") (class "Default")
      (node (ref "L_J10") (pin "2") (pinfunction "2_2") (pintype "bidirectional"))
    )
    (net (code "382") (name "unconnected-(L_J10-Pad35)") (class "Default")
      (node (ref "L_J10") (pin "35") (pinfunction "35_35") (pintype "bidirectional"))
    )
    (net (code "383") (name "unconnected-(L_J10-Pad39)") (class "Default")
      (node (ref "L_J10") (pin "39") (pinfunction "39_39") (pintype "bidirectional"))
    )
    (net (code "384") (name "~{ADD_BUF_EN}") (class "Default")
      (node (ref "IC2") (pin "19") (pinfunction "G_19") (pintype "input"))
      (node (ref "IC4") (pin "19") (pinfunction "G_19") (pintype "input"))
      (node (ref "L_J5") (pin "37") (pinfunction "37_37") (pintype "bidirectional"))
    )
    (net (code "385") (name "~{RAM_CS}") (class "Default")
      (node (ref "IC6") (pin "20") (pinfunction "~{CS}_20") (pintype "input"))
      (node (ref "L_J7") (pin "21") (pinfunction "21_21") (pintype "bidirectional"))
    )
    (net (code "386") (name "~{RAM_OE}") (class "Default")
      (node (ref "IC6") (pin "22") (pinfunction "~{OE}_22") (pintype "input"))
      (node (ref "L_J7") (pin "1") (pinfunction "1_1") (pintype "bidirectional"))
    )
    (net (code "387") (name "~{RAM_WE}") (class "Default")
      (node (ref "IC6") (pin "27") (pinfunction "~{WE}_27") (pintype "input"))
      (node (ref "L_J7") (pin "3") (pinfunction "3_3") (pintype "bidirectional"))
    )
    (net (code "388") (name "~{SPI_SS1}") (class "Default")
      (node (ref "IC8") (pin "8") (pinfunction "RC6_8") (pintype "bidirectional"))
      (node (ref "L_J7") (pin "30") (pinfunction "30_30") (pintype "bidirectional"))
    )
    (net (code "389") (name "~{SPI_SS2}") (class "Default")
      (node (ref "IC8") (pin "5") (pinfunction "RC5_5") (pintype "bidirectional"))
      (node (ref "L_J7") (pin "31") (pinfunction "31_31") (pintype "bidirectional"))
    )
  )
)
